# 15_BoardPowerSupply.net
KiCad netlist of a schematic drawn in Altium Designer
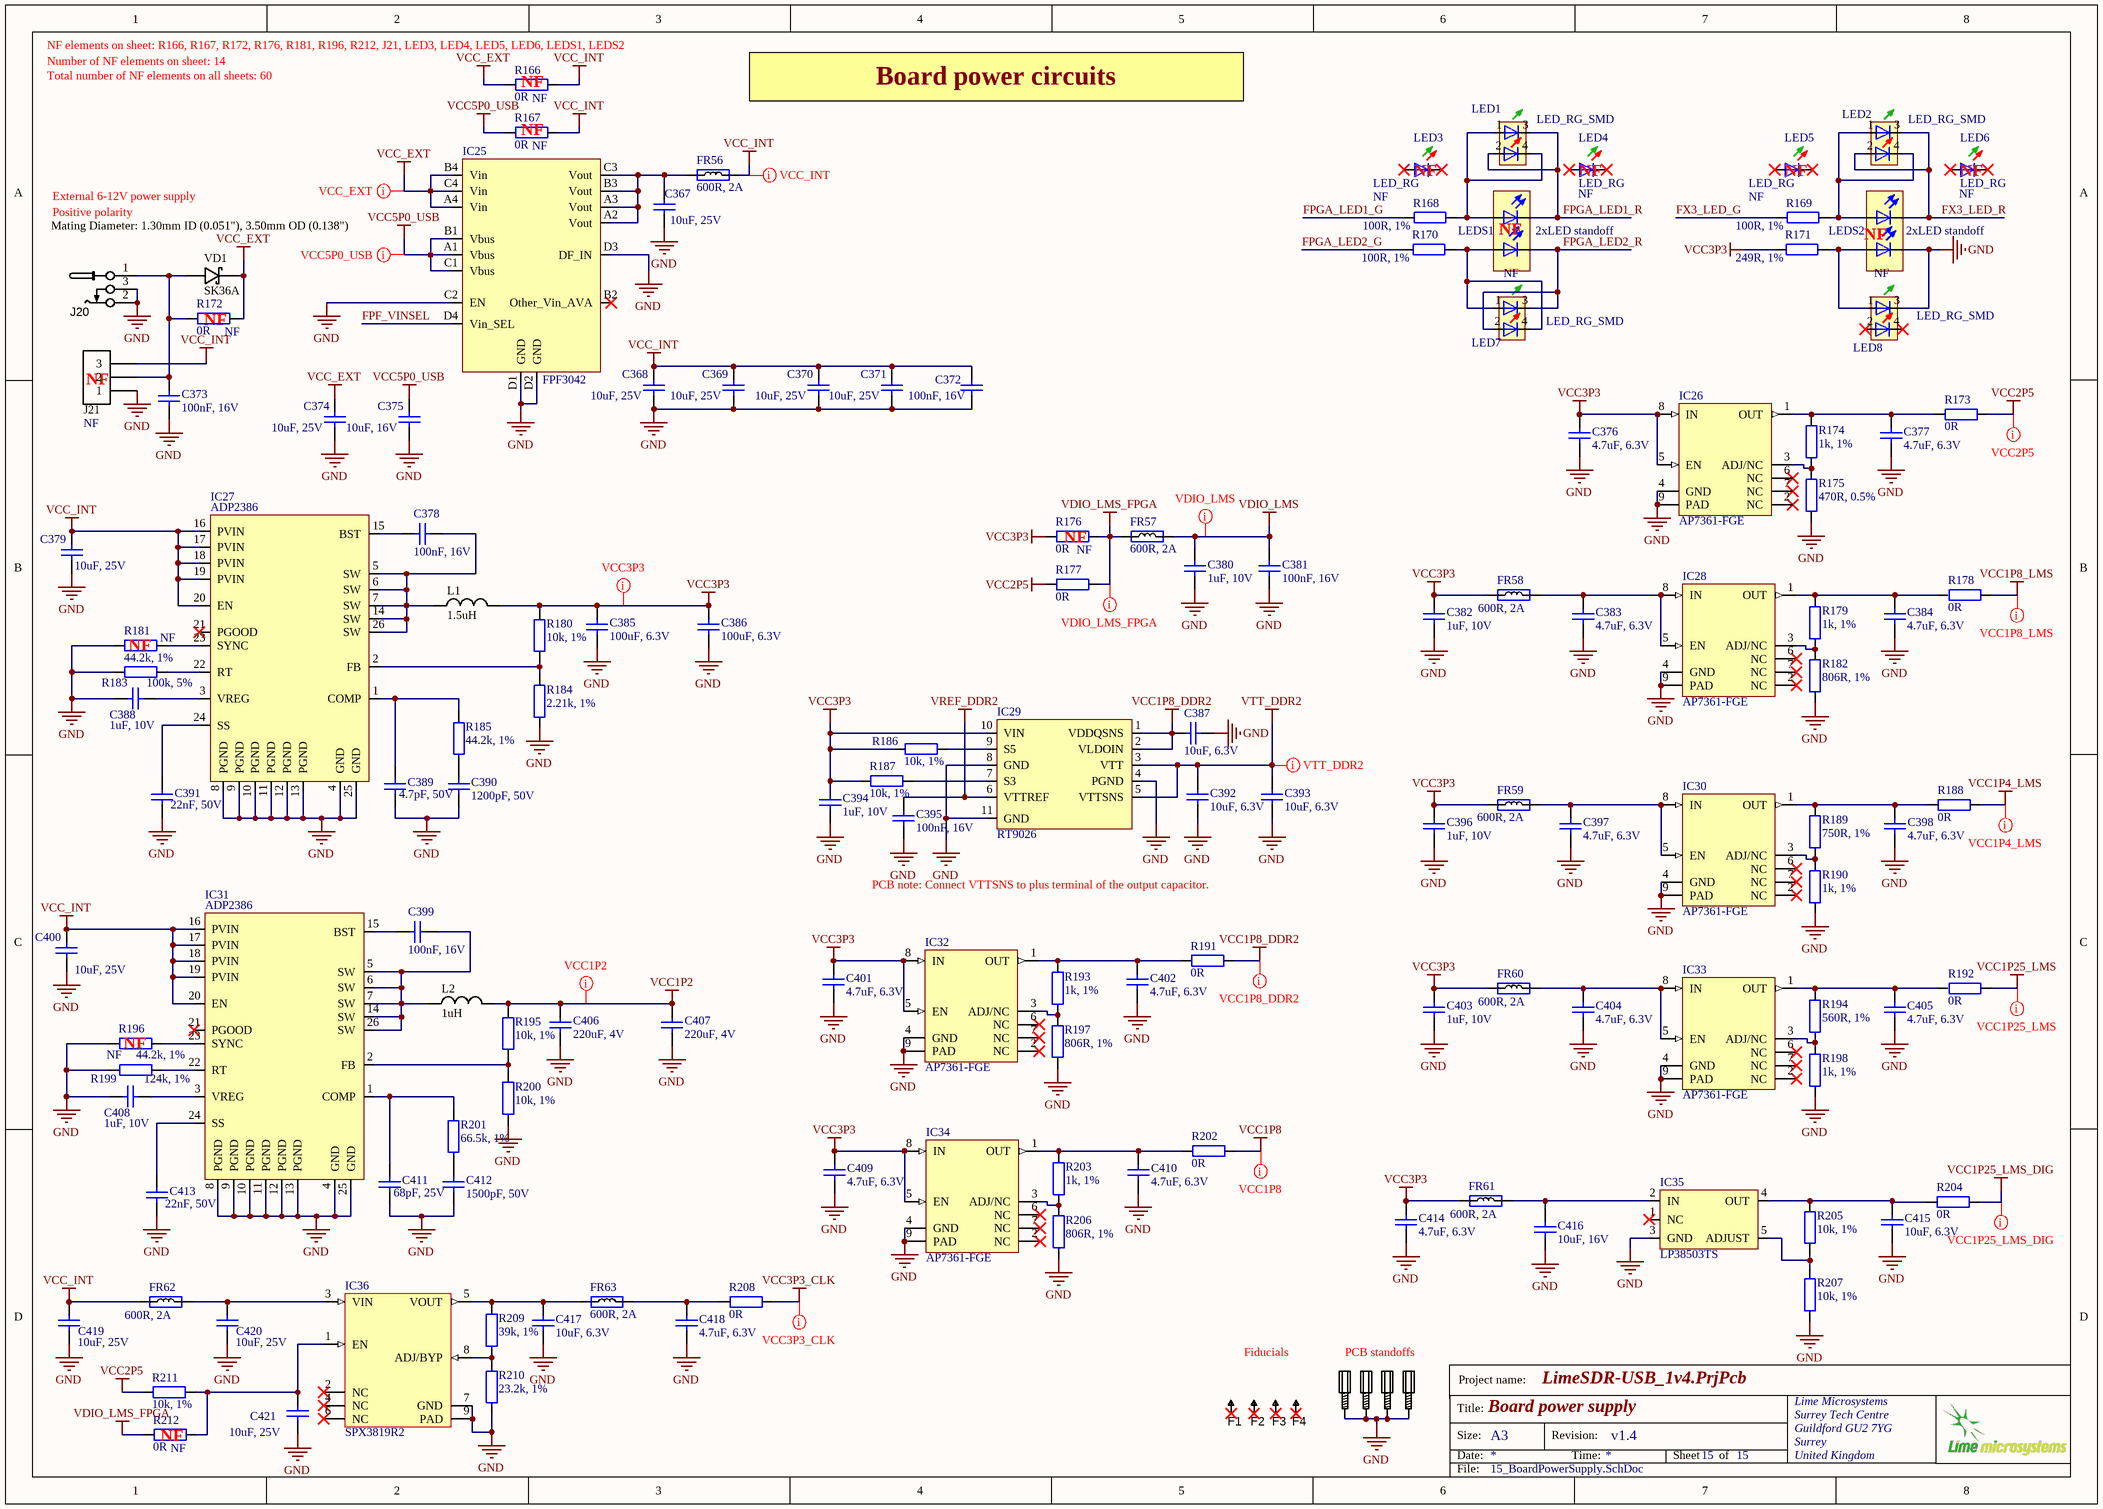
[diagram p0: 15_BoardPowerSupply.SchDoc]

(export (version "E")
  (design (tool "Eeschema 10.0.6"))
  (components
    (comp (ref "C367")
      (value "10uF, 25V")
      (footprint "CAP0603")
      (fields
        (field (name "MANUFACTURER") "Murata Electronics North America")
        (field (name "MANUFACTURER PART NUMBER") "GRM188R61E106MA73D")
        (field (name "TOLERANCE") "±20%")
      )
      (libsource (lib "LimeMicroAltiumLib_schLib") (part "Cap_0603"))
    )
    (comp (ref "C368")
      (value "10uF, 25V")
      (footprint "CAP0603")
      (fields
        (field (name "MANUFACTURER") "Murata Electronics North America")
        (field (name "MANUFACTURER PART NUMBER") "GRM188R61E106MA73D")
        (field (name "TOLERANCE") "±20%")
      )
      (libsource (lib "LimeMicroAltiumLib_schLib") (part "Cap_0603"))
    )
    (comp (ref "C369")
      (value "10uF, 25V")
      (footprint "CAP0603")
      (fields
        (field (name "MANUFACTURER") "Murata Electronics North America")
        (field (name "MANUFACTURER PART NUMBER") "GRM188R61E106MA73D")
        (field (name "TOLERANCE") "±20%")
      )
      (libsource (lib "LimeMicroAltiumLib_schLib") (part "Cap_0603"))
    )
    (comp (ref "C370")
      (value "10uF, 25V")
      (footprint "CAP0603")
      (fields
        (field (name "MANUFACTURER") "Murata Electronics North America")
        (field (name "MANUFACTURER PART NUMBER") "GRM188R61E106MA73D")
        (field (name "TOLERANCE") "±20%")
      )
      (libsource (lib "LimeMicroAltiumLib_schLib") (part "Cap_0603"))
    )
    (comp (ref "C371")
      (value "10uF, 25V")
      (footprint "CAP0603")
      (fields
        (field (name "MANUFACTURER") "Murata Electronics North America")
        (field (name "MANUFACTURER PART NUMBER") "GRM188R61E106MA73D")
        (field (name "TOLERANCE") "±20%")
      )
      (libsource (lib "LimeMicroAltiumLib_schLib") (part "Cap_0603"))
    )
    (comp (ref "C372")
      (value "100nF, 16V")
      (footprint "CAP0402")
      (fields
        (field (name "MANUFACTURER") "Murata Electronics")
        (field (name "TOLERANCE") "10 %")
        (field (name "MANUFACTURER PART NUMBER") "GRM155R71C104KA88D")
      )
      (libsource (lib "LimeMicroAltiumLib_schLib") (part "Cap_0402"))
    )
    (comp (ref "C373")
      (value "100nF, 16V")
      (footprint "CAP0402")
      (fields
        (field (name "MANUFACTURER") "Murata Electronics")
        (field (name "TOLERANCE") "10 %")
        (field (name "MANUFACTURER PART NUMBER") "GRM155R71C104KA88D")
      )
      (libsource (lib "LimeMicroAltiumLib_schLib") (part "Cap_0402"))
    )
    (comp (ref "C374")
      (value "10uF, 25V")
      (footprint "CAP0603")
      (fields
        (field (name "MANUFACTURER") "Murata Electronics North America")
        (field (name "MANUFACTURER PART NUMBER") "GRM188R61E106MA73D")
        (field (name "TOLERANCE") "±20%")
      )
      (libsource (lib "LimeMicroAltiumLib_schLib") (part "Cap_0603"))
    )
    (comp (ref "C375")
      (value "10uF, 16V")
      (footprint "CAP0603")
      (fields (field (name "MANUFACTURER") "Yageo") (field (name "TOLERANCE") "±20%"))
      (libsource (lib "LimeMicroAltiumLib_schLib") (part "Cap_0603"))
    )
    (comp (ref "C376")
      (value "4.7uF, 6.3V")
      (footprint "CAP0402")
      (fields
        (field (name "MANUFACTURER") "Murata Electronics North America")
        (field (name "TOLERANCE") "±20%")
        (field (name "MANUFACTURER PART NUMBER") "GRM155R60J475ME87D")
      )
      (libsource (lib "LimeMicroAltiumLib_schLib") (part "Cap_0402"))
    )
    (comp (ref "C377")
      (value "4.7uF, 6.3V")
      (footprint "CAP0402")
      (fields
        (field (name "MANUFACTURER") "Murata Electronics North America")
        (field (name "TOLERANCE") "±20%")
        (field (name "MANUFACTURER PART NUMBER") "GRM155R60J475ME87D")
      )
      (libsource (lib "LimeMicroAltiumLib_schLib") (part "Cap_0402"))
    )
    (comp (ref "C378")
      (value "100nF, 16V")
      (footprint "CAP0402")
      (fields
        (field (name "MANUFACTURER") "Murata Electronics")
        (field (name "TOLERANCE") "10 %")
        (field (name "MANUFACTURER PART NUMBER") "GRM155R71C104KA88D")
      )
      (libsource (lib "LimeMicroAltiumLib_schLib") (part "Cap_0402"))
    )
    (comp (ref "C379")
      (value "10uF, 25V")
      (footprint "CAP0603")
      (fields
        (field (name "MANUFACTURER") "Murata Electronics North America")
        (field (name "MANUFACTURER PART NUMBER") "GRM188R61E106MA73D")
        (field (name "TOLERANCE") "±20%")
      )
      (libsource (lib "LimeMicroAltiumLib_schLib") (part "Cap_0603"))
    )
    (comp (ref "C380")
      (value "1uF, 10V")
      (footprint "CAP0402")
      (fields (field (name "MANUFACTURER") "TDK"))
      (libsource (lib "LimeMicroAltiumLib_schLib") (part "Cap_0402"))
    )
    (comp (ref "C381")
      (value "100nF, 16V")
      (footprint "CAP0402")
      (fields
        (field (name "MANUFACTURER") "Murata Electronics")
        (field (name "TOLERANCE") "10 %")
        (field (name "MANUFACTURER PART NUMBER") "GRM155R71C104KA88D")
      )
      (libsource (lib "LimeMicroAltiumLib_schLib") (part "Cap_0402"))
    )
    (comp (ref "C382")
      (value "1uF, 10V")
      (footprint "CAP0402")
      (fields (field (name "MANUFACTURER") "TDK"))
      (libsource (lib "LimeMicroAltiumLib_schLib") (part "Cap_0402"))
    )
    (comp (ref "C383")
      (value "4.7uF, 6.3V")
      (footprint "CAP0402")
      (fields
        (field (name "MANUFACTURER") "Murata Electronics North America")
        (field (name "TOLERANCE") "±20%")
        (field (name "MANUFACTURER PART NUMBER") "GRM155R60J475ME87D")
      )
      (libsource (lib "LimeMicroAltiumLib_schLib") (part "Cap_0402"))
    )
    (comp (ref "C384")
      (value "4.7uF, 6.3V")
      (footprint "CAP0402")
      (fields
        (field (name "MANUFACTURER") "Murata Electronics North America")
        (field (name "TOLERANCE") "±20%")
        (field (name "MANUFACTURER PART NUMBER") "GRM155R60J475ME87D")
      )
      (libsource (lib "LimeMicroAltiumLib_schLib") (part "Cap_0402"))
    )
    (comp (ref "C385")
      (value "100uF, 6.3V")
      (footprint "CAP1206")
      (fields (field (name "MANUFACTURER") "Murata Electronics North America"))
      (libsource (lib "LimeFPGAboard_schLib") (part "Cap_1206"))
    )
    (comp (ref "C386")
      (value "100uF, 6.3V")
      (footprint "CAP1206")
      (fields (field (name "MANUFACTURER") "Murata Electronics North America"))
      (libsource (lib "LimeFPGAboard_schLib") (part "Cap_1206"))
    )
    (comp (ref "C387")
      (value "10uF, 6.3V")
      (footprint "CAP0603")
      (fields (field (name "TOLERANCE") "±20%") (field (name "MANUFACTURER") "Yageo"))
      (libsource (lib "LimeFPGAboard_schLib") (part "Cap_0603"))
    )
    (comp (ref "C388")
      (value "1uF, 10V")
      (footprint "CAP0402")
      (fields (field (name "MANUFACTURER") "TDK"))
      (libsource (lib "LimeMicroAltiumLib_schLib") (part "Cap_0402"))
    )
    (comp (ref "C389")
      (value "4.7pF, 50V")
      (footprint "CAP0402")
      (fields (field (name "MANUFACTURER") "Murata Electronics North America"))
      (libsource (lib "LimeMicroAltiumLib_schLib") (part "Cap_0402"))
    )
    (comp (ref "C390")
      (value "1200pF, 50V")
      (footprint "CAP0402")
      (fields (field (name "MANUFACTURER") "Kemet") (field (name "TOLERANCE") "±5%"))
      (libsource (lib "LimeMicroAltiumLib_schLib") (part "Cap_0402"))
    )
    (comp (ref "C391")
      (value "22nF, 50V")
      (footprint "CAP0402")
      (fields (field (name "TOLERANCE") "±10%") (field (name "MANUFACTURER") "Kemet"))
      (libsource (lib "LimeMicroAltiumLib_schLib") (part "Cap_0402"))
    )
    (comp (ref "C392")
      (value "10uF, 6.3V")
      (footprint "CAP0603")
      (fields (field (name "TOLERANCE") "±20%") (field (name "MANUFACTURER") "Yageo"))
      (libsource (lib "LimeFPGAboard_schLib") (part "Cap_0603"))
    )
    (comp (ref "C393")
      (value "10uF, 6.3V")
      (footprint "CAP0603")
      (fields (field (name "TOLERANCE") "±20%") (field (name "MANUFACTURER") "Yageo"))
      (libsource (lib "LimeFPGAboard_schLib") (part "Cap_0603"))
    )
    (comp (ref "C394")
      (value "1uF, 10V")
      (footprint "CAP0402")
      (fields (field (name "MANUFACTURER") "TDK"))
      (libsource (lib "LimeMicroAltiumLib_schLib") (part "Cap_0402"))
    )
    (comp (ref "C395")
      (value "100nF, 16V")
      (footprint "CAP0402")
      (fields
        (field (name "MANUFACTURER") "Murata Electronics")
        (field (name "TOLERANCE") "10 %")
        (field (name "MANUFACTURER PART NUMBER") "GRM155R71C104KA88D")
      )
      (libsource (lib "LimeMicroAltiumLib_schLib") (part "Cap_0402"))
    )
    (comp (ref "C396")
      (value "1uF, 10V")
      (footprint "CAP0402")
      (fields (field (name "MANUFACTURER") "TDK"))
      (libsource (lib "LimeMicroAltiumLib_schLib") (part "Cap_0402"))
    )
    (comp (ref "C397")
      (value "4.7uF, 6.3V")
      (footprint "CAP0402")
      (fields
        (field (name "MANUFACTURER") "Murata Electronics North America")
        (field (name "TOLERANCE") "±20%")
        (field (name "MANUFACTURER PART NUMBER") "GRM155R60J475ME87D")
      )
      (libsource (lib "LimeMicroAltiumLib_schLib") (part "Cap_0402"))
    )
    (comp (ref "C398")
      (value "4.7uF, 6.3V")
      (footprint "CAP0402")
      (fields
        (field (name "MANUFACTURER") "Murata Electronics North America")
        (field (name "TOLERANCE") "±20%")
        (field (name "MANUFACTURER PART NUMBER") "GRM155R60J475ME87D")
      )
      (libsource (lib "LimeMicroAltiumLib_schLib") (part "Cap_0402"))
    )
    (comp (ref "C399")
      (value "100nF, 16V")
      (footprint "CAP0402")
      (fields
        (field (name "MANUFACTURER") "Murata Electronics")
        (field (name "TOLERANCE") "10 %")
        (field (name "MANUFACTURER PART NUMBER") "GRM155R71C104KA88D")
      )
      (libsource (lib "LimeMicroAltiumLib_schLib") (part "Cap_0402"))
    )
    (comp (ref "C400")
      (value "10uF, 25V")
      (footprint "CAP0603")
      (fields
        (field (name "MANUFACTURER") "Murata Electronics North America")
        (field (name "MANUFACTURER PART NUMBER") "GRM188R61E106MA73D")
        (field (name "TOLERANCE") "±20%")
      )
      (libsource (lib "LimeMicroAltiumLib_schLib") (part "Cap_0603"))
    )
    (comp (ref "C401")
      (value "4.7uF, 6.3V")
      (footprint "CAP0402")
      (fields
        (field (name "MANUFACTURER") "Murata Electronics North America")
        (field (name "TOLERANCE") "±20%")
        (field (name "MANUFACTURER PART NUMBER") "GRM155R60J475ME87D")
      )
      (libsource (lib "LimeMicroAltiumLib_schLib") (part "Cap_0402"))
    )
    (comp (ref "C402")
      (value "4.7uF, 6.3V")
      (footprint "CAP0402")
      (fields
        (field (name "MANUFACTURER") "Murata Electronics North America")
        (field (name "TOLERANCE") "±20%")
        (field (name "MANUFACTURER PART NUMBER") "GRM155R60J475ME87D")
      )
      (libsource (lib "LimeMicroAltiumLib_schLib") (part "Cap_0402"))
    )
    (comp (ref "C403")
      (value "1uF, 10V")
      (footprint "CAP0402")
      (fields (field (name "MANUFACTURER") "TDK"))
      (libsource (lib "LimeMicroAltiumLib_schLib") (part "Cap_0402"))
    )
    (comp (ref "C404")
      (value "4.7uF, 6.3V")
      (footprint "CAP0402")
      (fields
        (field (name "MANUFACTURER") "Murata Electronics North America")
        (field (name "TOLERANCE") "±20%")
        (field (name "MANUFACTURER PART NUMBER") "GRM155R60J475ME87D")
      )
      (libsource (lib "LimeMicroAltiumLib_schLib") (part "Cap_0402"))
    )
    (comp (ref "C405")
      (value "4.7uF, 6.3V")
      (footprint "CAP0402")
      (fields
        (field (name "MANUFACTURER") "Murata Electronics North America")
        (field (name "TOLERANCE") "±20%")
        (field (name "MANUFACTURER PART NUMBER") "GRM155R60J475ME87D")
      )
      (libsource (lib "LimeMicroAltiumLib_schLib") (part "Cap_0402"))
    )
    (comp (ref "C406")
      (value "220uF, 4V")
      (footprint "CAP1206")
      (fields
        (field (name "MANUFACTURER") "Murata Electronics North America")
        (field (name "TOLERANCE") "±20%")
        (field (name "MANUFACTURER PART NUMBER") "GRM31CR60G227ME11L")
      )
      (libsource (lib "LimeFPGAboard_schLib") (part "Cap_1206"))
    )
    (comp (ref "C407")
      (value "220uF, 4V")
      (footprint "CAP1206")
      (fields
        (field (name "MANUFACTURER") "Murata Electronics North America")
        (field (name "TOLERANCE") "±20%")
        (field (name "MANUFACTURER PART NUMBER") "GRM31CR60G227ME11L")
      )
      (libsource (lib "LimeFPGAboard_schLib") (part "Cap_1206"))
    )
    (comp (ref "C408")
      (value "1uF, 10V")
      (footprint "CAP0402")
      (fields (field (name "MANUFACTURER") "TDK"))
      (libsource (lib "LimeMicroAltiumLib_schLib") (part "Cap_0402"))
    )
    (comp (ref "C409")
      (value "4.7uF, 6.3V")
      (footprint "CAP0402")
      (fields
        (field (name "MANUFACTURER") "Murata Electronics North America")
        (field (name "TOLERANCE") "±20%")
        (field (name "MANUFACTURER PART NUMBER") "GRM155R60J475ME87D")
      )
      (libsource (lib "LimeMicroAltiumLib_schLib") (part "Cap_0402"))
    )
    (comp (ref "C410")
      (value "4.7uF, 6.3V")
      (footprint "CAP0402")
      (fields
        (field (name "MANUFACTURER") "Murata Electronics North America")
        (field (name "TOLERANCE") "±20%")
        (field (name "MANUFACTURER PART NUMBER") "GRM155R60J475ME87D")
      )
      (libsource (lib "LimeMicroAltiumLib_schLib") (part "Cap_0402"))
    )
    (comp (ref "C411")
      (value "68pF, 25V")
      (footprint "CAP0402")
      (fields (field (name "TOLERANCE") "±1%") (field (name "MANUFACTURER") "Kemet"))
      (libsource (lib "LimeMicroAltiumLib_schLib") (part "Cap_0402"))
    )
    (comp (ref "C412")
      (value "1500pF, 50V")
      (footprint "CAP0402")
      (fields
        (field (name "MANUFACTURER") "Samsung Electro-Mechanics America, Inc.")
        (field (name "TOLERANCE") "±10%")
      )
      (libsource (lib "LimeMicroAltiumLib_schLib") (part "Cap_0402"))
    )
    (comp (ref "C413")
      (value "22nF, 50V")
      (footprint "CAP0402")
      (fields (field (name "TOLERANCE") "±10%") (field (name "MANUFACTURER") "Kemet"))
      (libsource (lib "LimeMicroAltiumLib_schLib") (part "Cap_0402"))
    )
    (comp (ref "C414")
      (value "4.7uF, 6.3V")
      (footprint "CAP0402")
      (fields
        (field (name "MANUFACTURER") "Murata Electronics North America")
        (field (name "TOLERANCE") "±20%")
        (field (name "MANUFACTURER PART NUMBER") "GRM155R60J475ME87D")
      )
      (libsource (lib "LimeMicroAltiumLib_schLib") (part "Cap_0402"))
    )
    (comp (ref "C415")
      (value "10uF, 6.3V")
      (footprint "CAP0603")
      (fields (field (name "TOLERANCE") "±20%") (field (name "MANUFACTURER") "Yageo"))
      (libsource (lib "LimeFPGAboard_schLib") (part "Cap_0603"))
    )
    (comp (ref "C416")
      (value "10uF, 16V")
      (footprint "CAP0603")
      (fields (field (name "MANUFACTURER") "Yageo") (field (name "TOLERANCE") "±20%"))
      (libsource (lib "LimeMicroAltiumLib_schLib") (part "Cap_0603"))
    )
    (comp (ref "C417")
      (value "10uF, 6.3V")
      (footprint "CAP0603")
      (fields (field (name "TOLERANCE") "±20%") (field (name "MANUFACTURER") "Yageo"))
      (libsource (lib "LimeFPGAboard_schLib") (part "Cap_0603"))
    )
    (comp (ref "C418")
      (value "4.7uF, 6.3V")
      (footprint "CAP0402")
      (fields
        (field (name "MANUFACTURER") "Murata Electronics North America")
        (field (name "TOLERANCE") "±20%")
        (field (name "MANUFACTURER PART NUMBER") "GRM155R60J475ME87D")
      )
      (libsource (lib "LimeMicroAltiumLib_schLib") (part "Cap_0402"))
    )
    (comp (ref "C419")
      (value "10uF, 25V")
      (footprint "CAP0603")
      (fields
        (field (name "MANUFACTURER") "Murata Electronics North America")
        (field (name "MANUFACTURER PART NUMBER") "GRM188R61E106MA73D")
        (field (name "TOLERANCE") "±20%")
      )
      (libsource (lib "LimeMicroAltiumLib_schLib") (part "Cap_0603"))
    )
    (comp (ref "C420")
      (value "10uF, 25V")
      (footprint "CAP0603")
      (fields
        (field (name "MANUFACTURER") "Murata Electronics North America")
        (field (name "MANUFACTURER PART NUMBER") "GRM188R61E106MA73D")
        (field (name "TOLERANCE") "±20%")
      )
      (libsource (lib "LimeMicroAltiumLib_schLib") (part "Cap_0603"))
    )
    (comp (ref "C421")
      (value "10uF, 25V")
      (footprint "CAP0603")
      (fields
        (field (name "MANUFACTURER") "Murata Electronics North America")
        (field (name "MANUFACTURER PART NUMBER") "GRM188R61E106MA73D")
        (field (name "TOLERANCE") "±20%")
      )
      (libsource (lib "LimeMicroAltiumLib_schLib") (part "Cap_0603"))
    )
    (comp (ref "F1")
      (value "Fiducial")
      (footprint "Fiducial")
      (libsource (lib "VGTU_Altium_lib") (part "Fiducial"))
    )
    (comp (ref "F2")
      (value "Fiducial")
      (footprint "Fiducial")
      (libsource (lib "VGTU_Altium_lib") (part "Fiducial"))
    )
    (comp (ref "F3")
      (value "Fiducial")
      (footprint "Fiducial")
      (libsource (lib "VGTU_Altium_lib") (part "Fiducial"))
    )
    (comp (ref "F4")
      (value "Fiducial")
      (footprint "Fiducial")
      (libsource (lib "VGTU_Altium_lib") (part "Fiducial"))
    )
    (comp (ref "FR56")
      (value "600R, 2A")
      (footprint "RES0805")
      (fields (field (name "MANUFACTURER") "TDK Corporation"))
      (libsource (lib "LimeFPGAboard_schLib") (part "Ferrite"))
    )
    (comp (ref "FR57")
      (value "600R, 2A")
      (footprint "RES0805")
      (fields (field (name "MANUFACTURER") "TDK Corporation"))
      (libsource (lib "LimeMicroAltiumLib_schLib") (part "Ferrite"))
    )
    (comp (ref "FR58")
      (value "600R, 2A")
      (footprint "RES0805")
      (fields (field (name "MANUFACTURER") "TDK Corporation"))
      (libsource (lib "LimeMicroAltiumLib_schLib") (part "Ferrite"))
    )
    (comp (ref "FR59")
      (value "600R, 2A")
      (footprint "RES0805")
      (fields (field (name "MANUFACTURER") "TDK Corporation"))
      (libsource (lib "LimeMicroAltiumLib_schLib") (part "Ferrite"))
    )
    (comp (ref "FR60")
      (value "600R, 2A")
      (footprint "RES0805")
      (fields (field (name "MANUFACTURER") "TDK Corporation"))
      (libsource (lib "LimeMicroAltiumLib_schLib") (part "Ferrite"))
    )
    (comp (ref "FR61")
      (value "600R, 2A")
      (footprint "RES0805")
      (fields (field (name "MANUFACTURER") "TDK Corporation"))
      (libsource (lib "LimeMicroAltiumLib_schLib") (part "Ferrite"))
    )
    (comp (ref "FR62")
      (value "600R, 2A")
      (footprint "RES0805")
      (fields (field (name "MANUFACTURER") "TDK Corporation"))
      (libsource (lib "LimeMicroAltiumLib_schLib") (part "Ferrite"))
    )
    (comp (ref "FR63")
      (value "600R, 2A")
      (footprint "RES0805")
      (fields (field (name "MANUFACTURER") "TDK Corporation"))
      (libsource (lib "LimeMicroAltiumLib_schLib") (part "Ferrite"))
    )
    (comp (ref "IC25")
      (value "FPF3042")
      (footprint "FPF3042")
      (fields (field (name "MANUFACTURER") "Fairchild Semiconductor"))
      (libsource (lib "LimeMicroAltiumLib_schLib") (part "FPF3042"))
    )
    (comp (ref "IC26")
      (value "AP7361-FGE")
      (footprint "AP7361")
      (fields
        (field (name "MANUFACTURER PART NUMBER") "AP7361-FGE-7")
        (field (name "MANUFACTURER") "Diodes Incorporated")
      )
      (libsource (lib "LimeMicroAltiumLib_schLib") (part "AP7361"))
    )
    (comp (ref "IC27")
      (value "ADP2386")
      (footprint "ADP2386")
      (fields
        (field (name "MANUFACTURER PART NUMBER") "ADP2386ACPZN-R7")
        (field (name "MANUFACTURER") "Analog Devices Inc.")
      )
      (libsource (lib "LimeMicroAltiumLib_schLib") (part "ADP2386"))
    )
    (comp (ref "IC28")
      (value "AP7361-FGE")
      (footprint "AP7361")
      (fields
        (field (name "MANUFACTURER PART NUMBER") "AP7361-FGE-7")
        (field (name "MANUFACTURER") "Diodes Incorporated")
      )
      (libsource (lib "LimeMicroAltiumLib_schLib") (part "AP7361"))
    )
    (comp (ref "IC29")
      (value "RT9026")
      (footprint "MSOP10")
      (fields (field (name "MANUFACTURER") "Richtek USA Inc."))
      (libsource (lib "LimeMicroAltiumLib_schLib") (part "RT9026"))
    )
    (comp (ref "IC30")
      (value "AP7361-FGE")
      (footprint "AP7361")
      (fields
        (field (name "MANUFACTURER PART NUMBER") "AP7361-FGE-7")
        (field (name "MANUFACTURER") "Diodes Incorporated")
      )
      (libsource (lib "LimeMicroAltiumLib_schLib") (part "AP7361"))
    )
    (comp (ref "IC31")
      (value "ADP2386")
      (footprint "ADP2386")
      (fields (field (name "MANUFACTURER") "Analog Devices Inc."))
      (libsource (lib "LimeMicroAltiumLib_schLib") (part "ADP2386"))
    )
    (comp (ref "IC32")
      (value "AP7361-FGE")
      (footprint "AP7361")
      (fields
        (field (name "MANUFACTURER PART NUMBER") "AP7361-FGE-7")
        (field (name "MANUFACTURER") "Diodes Incorporated")
      )
      (libsource (lib "LimeMicroAltiumLib_schLib") (part "AP7361"))
    )
    (comp (ref "IC33")
      (value "AP7361-FGE")
      (footprint "AP7361")
      (fields
        (field (name "MANUFACTURER PART NUMBER") "AP7361-FGE-7")
        (field (name "MANUFACTURER") "Diodes Incorporated")
      )
      (libsource (lib "LimeMicroAltiumLib_schLib") (part "AP7361"))
    )
    (comp (ref "IC34")
      (value "AP7361-FGE")
      (footprint "AP7361")
      (fields
        (field (name "MANUFACTURER PART NUMBER") "AP7361-FGE-7")
        (field (name "MANUFACTURER") "Diodes Incorporated")
      )
      (libsource (lib "LimeMicroAltiumLib_schLib") (part "AP7361"))
    )
    (comp (ref "IC35")
      (value "LP38503TS")
      (footprint "TO-263-5_v2")
      (fields
        (field (name "MANUFACTURER PART NUMBER") "LP38503TS-ADJ/NOPB")
        (field (name "MANUFACTURER") "Texas Instruments")
      )
      (libsource (lib "LimeMicroAltiumLib_schLib") (part "LP38503TS"))
    )
    (comp (ref "IC36")
      (value "SPX3819R2")
      (footprint "SPX3819R2-L/TR")
      (fields (field (name "MANUFACTURER") "Exar Corporation"))
      (libsource (lib "LimeMicroAltiumLib_schLib") (part "SPX3819R2-L/TR"))
    )
    (comp (ref "J20")
      (value "Mating Diameter: 1.30mm ID (0.051\"), 3.50mm OD (0.138\")")
      (footprint "CONN_PWR_JACK_v4")
      (fields (field (name "MANUFACTURER") "CUI Inc."))
      (libsource (lib "LimeFPGAboard_schLib") (part "CONN_PWR_JACK_2.1x5.5mm"))
    )
    (comp (ref "J21")
      (value "Header 3x1 pin")
      (footprint "HDR_1x3")
      (description "Header, 3-pin")
      (fields (field (name "ASSEMBLY INFO") "NF") (field (name "MANUFACTURER") "Amphenol FCI"))
      (libsource (lib "LimeMicroAltiumLib_schLib") (part "Header3P"))
    )
    (comp (ref "L1")
      (value "1.5uH")
      (footprint "FDVE1040_TOKO_INDUCTOR")
      (fields (field (name "MANUFACTURER") "Vishay Dale") (field (name "TOLERANCE") "±20%"))
      (libsource (lib "LimeMicroAltiumLib_schLib") (part "Inductor_0603"))
    )
    (comp (ref "L2")
      (value "1uH")
      (footprint "FDVE1040_TOKO_INDUCTOR")
      (fields (field (name "TOLERANCE") "±20%") (field (name "MANUFACTURER") "Vishay Dale"))
      (libsource (lib "LimeMicroAltiumLib_schLib") (part "Inductor_0603"))
    )
    (comp (ref "LED1")
      (value "LED_RG_SMD")
      (footprint "LED-2x0603")
      (fields (field (name "MANUFACTURER") "Avago Technologies US Inc."))
      (libsource (lib "LimeMicroAltiumLib_schLib") (part "LED_green_red_SMD"))
    )
    (comp (ref "LED2")
      (value "LED_RG_SMD")
      (footprint "LED-2x0603")
      (fields (field (name "MANUFACTURER") "Avago Technologies US Inc."))
      (libsource (lib "LimeMicroAltiumLib_schLib") (part "LED_green_red_SMD"))
    )
    (comp (ref "LED3")
      (value "LED_RG")
      (fields
        (field (name "MANUFACTURER") "Visual Communications Company - VCC")
        (field (name "ASSEMBLY INFO") "NF")
      )
      (libsource (lib "LimeMicroAltiumLib_schLib") (part "LED_green_red"))
    )
    (comp (ref "LED4")
      (value "LED_RG")
      (fields
        (field (name "MANUFACTURER") "Visual Communications Company - VCC")
        (field (name "ASSEMBLY INFO") "NF")
      )
      (libsource (lib "LimeMicroAltiumLib_schLib") (part "LED_green_red"))
    )
    (comp (ref "LED5")
      (value "LED_RG")
      (fields
        (field (name "MANUFACTURER") "Visual Communications Company - VCC")
        (field (name "ASSEMBLY INFO") "NF")
      )
      (libsource (lib "LimeMicroAltiumLib_schLib") (part "LED_green_red"))
    )
    (comp (ref "LED6")
      (value "LED_RG")
      (fields
        (field (name "MANUFACTURER") "Visual Communications Company - VCC")
        (field (name "ASSEMBLY INFO") "NF")
      )
      (libsource (lib "LimeMicroAltiumLib_schLib") (part "LED_green_red"))
    )
    (comp (ref "LED7")
      (value "LED_RG_SMD")
      (footprint "LED-2x0603")
      (fields (field (name "MANUFACTURER") "Avago Technologies US Inc."))
      (libsource (lib "LimeMicroAltiumLib_schLib") (part "LED_green_red_SMD"))
    )
    (comp (ref "LED8")
      (value "LED_RG_SMD")
      (footprint "LED-2x0603")
      (fields (field (name "MANUFACTURER") "Avago Technologies US Inc."))
      (libsource (lib "LimeMicroAltiumLib_schLib") (part "LED_green_red_SMD"))
    )
    (comp (ref "LEDS1")
      (value "2xLED standoff")
      (footprint "LED_STANDOFF_H-201C")
      (fields (field (name "MANUFACTURER") "Bivar Inc.") (field (name "ASSEMBLY INFO") "NF"))
      (libsource (lib "LimeMicroAltiumLib_schLib") (part "LEDx2_STANDOFF"))
    )
    (comp (ref "LEDS2")
      (value "2xLED standoff")
      (footprint "LED_STANDOFF_H-201C")
      (fields (field (name "MANUFACTURER") "Bivar Inc.") (field (name "ASSEMBLY INFO") "NF"))
      (libsource (lib "LimeMicroAltiumLib_schLib") (part "LEDx2_STANDOFF"))
    )
    (comp (ref "MECH1")
      (value "# pcs.")
      (footprint "PCB_standoff")
      (description "STANDOFF M/F MET 5MM HEX 10MM L")
      (fields (field (name "MANUFACTURER") "FIX&FASTEN"))
      (libsource (lib "LimeMicroAltiumLib_schLib") (part "STANDOFF_M-F_THREADED_M3x8x10mm_HEX_5mm dia"))
    )
    (comp (ref "MECH2")
      (value "# pcs.")
      (footprint "PCB_standoff")
      (description "STANDOFF M/F MET 5MM HEX 10MM L")
      (fields (field (name "MANUFACTURER") "FIX&FASTEN"))
      (libsource (lib "LimeMicroAltiumLib_schLib") (part "STANDOFF_M-F_THREADED_M3x8x10mm_HEX_5mm dia"))
    )
    (comp (ref "MECH3")
      (value "# pcs.")
      (footprint "PCB_standoff")
      (description "STANDOFF M/F MET 5MM HEX 10MM L")
      (fields (field (name "MANUFACTURER") "FIX&FASTEN"))
      (libsource (lib "LimeMicroAltiumLib_schLib") (part "STANDOFF_M-F_THREADED_M3x8x10mm_HEX_5mm dia"))
    )
    (comp (ref "MECH4")
      (value "# pcs.")
      (footprint "PCB_standoff")
      (description "STANDOFF M/F MET 5MM HEX 10MM L")
      (fields (field (name "MANUFACTURER") "FIX&FASTEN"))
      (libsource (lib "LimeMicroAltiumLib_schLib") (part "STANDOFF_M-F_THREADED_M3x8x10mm_HEX_5mm dia"))
    )
    (comp (ref "R166")
      (value "0R")
      (footprint "RES0402")
      (fields
        (field (name "ASSEMBLY INFO") "NF")
        (field (name "MANUFACTURER") "Yageo")
        (field (name "TOLERANCE") "Jumper")
      )
      (libsource (lib "LimeMicroAltiumLib_schLib") (part "Res_0402"))
    )
    (comp (ref "R167")
      (value "0R")
      (footprint "RES0402")
      (fields
        (field (name "ASSEMBLY INFO") "NF")
        (field (name "MANUFACTURER") "Yageo")
        (field (name "TOLERANCE") "Jumper")
      )
      (libsource (lib "LimeMicroAltiumLib_schLib") (part "Res_0402"))
    )
    (comp (ref "R168")
      (value "100R, 1%")
      (footprint "RES0402")
      (fields (field (name "TOLERANCE") "±1%") (field (name "MANUFACTURER") "Stackpole Electronics Inc."))
      (libsource (lib "LimeMicroAltiumLib_schLib") (part "Res_0402"))
    )
    (comp (ref "R169")
      (value "100R, 1%")
      (footprint "RES0402")
      (fields (field (name "TOLERANCE") "±1%") (field (name "MANUFACTURER") "Stackpole Electronics Inc."))
      (libsource (lib "LimeMicroAltiumLib_schLib") (part "Res_0402"))
    )
    (comp (ref "R170")
      (value "100R, 1%")
      (footprint "RES0402")
      (fields (field (name "TOLERANCE") "±1%") (field (name "MANUFACTURER") "Stackpole Electronics Inc."))
      (libsource (lib "LimeMicroAltiumLib_schLib") (part "Res_0402"))
    )
    (comp (ref "R171")
      (value "249R, 1%")
      (footprint "RES0402")
      (fields (field (name "MANUFACTURER") "Stackpole Electronics Inc") (field (name "TOLERANCE") "±1%"))
      (libsource (lib "LimeMicroAltiumLib_schLib") (part "Res_0402"))
    )
    (comp (ref "R172")
      (value "0R")
      (footprint "RES0805")
      (fields
        (field (name "ASSEMBLY INFO") "NF")
        (field (name "MANUFACTURER") "Vishay Dale")
        (field (name "TOLERANCE") "Jumper")
      )
      (libsource (lib "LimeMicroAltiumLib_schLib") (part "Res_0402"))
    )
    (comp (ref "R173")
      (value "0R")
      (footprint "RES0402")
      (fields (field (name "MANUFACTURER") "Yageo") (field (name "TOLERANCE") "Jumper"))
      (libsource (lib "LimeMicroAltiumLib_schLib") (part "Res_0402"))
    )
    (comp (ref "R174")
      (value "1k, 1%")
      (footprint "RES0402")
      (fields (field (name "MANUFACTURER") "Stackpole Electronics Inc") (field (name "TOLERANCE") "±1%"))
      (libsource (lib "LimeMicroAltiumLib_schLib") (part "Res_0402"))
    )
    (comp (ref "R175")
      (value "470R, 0.5%")
      (footprint "RES0402")
      (fields
        (field (name "TOLERANCE") "±0.5%")
        (field (name "MANUFACTURER") "Panasonic Electronic Components")
      )
      (libsource (lib "LimeMicroAltiumLib_schLib") (part "Res_0402"))
    )
    (comp (ref "R176")
      (value "0R")
      (footprint "RES0402")
      (fields
        (field (name "ASSEMBLY INFO") "NF")
        (field (name "MANUFACTURER") "Yageo")
        (field (name "TOLERANCE") "Jumper")
      )
      (libsource (lib "LimeMicroAltiumLib_schLib") (part "Res_0402"))
    )
    (comp (ref "R177")
      (value "0R")
      (footprint "RES0402")
      (fields (field (name "MANUFACTURER") "Yageo") (field (name "TOLERANCE") "Jumper"))
      (libsource (lib "LimeMicroAltiumLib_schLib") (part "Res_0402"))
    )
    (comp (ref "R178")
      (value "0R")
      (footprint "RES0402")
      (fields (field (name "MANUFACTURER") "Yageo") (field (name "TOLERANCE") "Jumper"))
      (libsource (lib "LimeMicroAltiumLib_schLib") (part "Res_0402"))
    )
    (comp (ref "R179")
      (value "1k, 1%")
      (footprint "RES0402")
      (fields (field (name "MANUFACTURER") "Stackpole Electronics Inc") (field (name "TOLERANCE") "±1%"))
      (libsource (lib "LimeMicroAltiumLib_schLib") (part "Res_0402"))
    )
    (comp (ref "R180")
      (value "10k, 1%")
      (footprint "RES0402")
      (fields (field (name "MANUFACTURER") "Yageo") (field (name "TOLERANCE") "±1%"))
      (libsource (lib "LimeMicroAltiumLib_schLib") (part "Res_0402"))
    )
    (comp (ref "R181")
      (value "44.2k, 1%")
      (footprint "RES0402")
      (fields
        (field (name "ASSEMBLY INFO") "NF")
        (field (name "TOLERANCE") "±1%")
        (field (name "MANUFACTURER") "Panasonic Electronic Components")
      )
      (libsource (lib "LimeMicroAltiumLib_schLib") (part "Res_0402"))
    )
    (comp (ref "R182")
      (value "806R, 1%")
      (footprint "RES0402")
      (fields (field (name "TOLERANCE") "±1%") (field (name "MANUFACTURER") "Stackpole Electronics Inc"))
      (libsource (lib "LimeMicroAltiumLib_schLib") (part "Res_0402"))
    )
    (comp (ref "R183")
      (value "100k, 5%")
      (footprint "RES0402")
      (fields
        (field (name "MANUFACTURER") "Panasonic Electronic Components")
        (field (name "MANUFACTURER PART NUMBER") "ERJ-2GEJ104X")
        (field (name "TOLERANCE") "±5%")
      )
      (libsource (lib "LimeMicroAltiumLib_schLib") (part "Res_0402"))
    )
    (comp (ref "R184")
      (value "2.21k, 1%")
      (footprint "RES0402")
      (fields (field (name "MANUFACTURER") "Stackpole Electronics Inc.") (field (name "TOLERANCE") "±1%"))
      (libsource (lib "LimeMicroAltiumLib_schLib") (part "Res_0402"))
    )
    (comp (ref "R185")
      (value "44.2k, 1%")
      (footprint "RES0402")
      (fields
        (field (name "TOLERANCE") "±1%")
        (field (name "MANUFACTURER") "Panasonic Electronic Components")
      )
      (libsource (lib "LimeMicroAltiumLib_schLib") (part "Res_0402"))
    )
    (comp (ref "R186")
      (value "10k, 1%")
      (footprint "RES0402")
      (fields (field (name "MANUFACTURER") "Yageo") (field (name "TOLERANCE") "±1%"))
      (libsource (lib "LimeMicroAltiumLib_schLib") (part "Res_0402"))
    )
    (comp (ref "R187")
      (value "10k, 1%")
      (footprint "RES0402")
      (fields (field (name "MANUFACTURER") "Yageo") (field (name "TOLERANCE") "±1%"))
      (libsource (lib "LimeMicroAltiumLib_schLib") (part "Res_0402"))
    )
    (comp (ref "R188")
      (value "0R")
      (footprint "RES0402")
      (fields (field (name "MANUFACTURER") "Yageo") (field (name "TOLERANCE") "Jumper"))
      (libsource (lib "LimeMicroAltiumLib_schLib") (part "Res_0402"))
    )
    (comp (ref "R189")
      (value "750R, 1%")
      (footprint "RES0402")
      (fields
        (field (name "TOLERANCE") "±1%")
        (field (name "MANUFACTURER PART NUMBER") "RC0402FR-07750RL")
        (field (name "MANUFACTURER") "Yageo")
      )
      (libsource (lib "LimeMicroAltiumLib_schLib") (part "Res_0402"))
    )
    (comp (ref "R190")
      (value "1k, 1%")
      (footprint "RES0402")
      (fields (field (name "MANUFACTURER") "Stackpole Electronics Inc") (field (name "TOLERANCE") "±1%"))
      (libsource (lib "LimeMicroAltiumLib_schLib") (part "Res_0402"))
    )
    (comp (ref "R191")
      (value "0R")
      (footprint "RES0402")
      (fields (field (name "MANUFACTURER") "Yageo") (field (name "TOLERANCE") "Jumper"))
      (libsource (lib "LimeMicroAltiumLib_schLib") (part "Res_0402"))
    )
    (comp (ref "R192")
      (value "0R")
      (footprint "RES0402")
      (fields (field (name "MANUFACTURER") "Yageo") (field (name "TOLERANCE") "Jumper"))
      (libsource (lib "LimeMicroAltiumLib_schLib") (part "Res_0402"))
    )
    (comp (ref "R193")
      (value "1k, 1%")
      (footprint "RES0402")
      (fields (field (name "MANUFACTURER") "Stackpole Electronics Inc") (field (name "TOLERANCE") "±1%"))
      (libsource (lib "LimeMicroAltiumLib_schLib") (part "Res_0402"))
    )
    (comp (ref "R194")
      (value "560R, 1%")
      (footprint "RES0402")
      (fields
        (field (name "MANUFACTURER PART NUMBER") "CRCW0402560RFKED")
        (field (name "TOLERANCE") "±1%")
        (field (name "MANUFACTURER") "Vishay Dale")
      )
      (libsource (lib "LimeMicroAltiumLib_schLib") (part "Res_0402"))
    )
    (comp (ref "R195")
      (value "10k, 1%")
      (footprint "RES0402")
      (fields (field (name "MANUFACTURER") "Yageo") (field (name "TOLERANCE") "±1%"))
      (libsource (lib "LimeMicroAltiumLib_schLib") (part "Res_0402"))
    )
    (comp (ref "R196")
      (value "44.2k, 1%")
      (footprint "RES0402")
      (fields
        (field (name "ASSEMBLY INFO") "NF")
        (field (name "TOLERANCE") "±1%")
        (field (name "MANUFACTURER") "Panasonic Electronic Components")
      )
      (libsource (lib "LimeMicroAltiumLib_schLib") (part "Res_0402"))
    )
    (comp (ref "R197")
      (value "806R, 1%")
      (footprint "RES0402")
      (fields (field (name "TOLERANCE") "±1%") (field (name "MANUFACTURER") "Stackpole Electronics Inc"))
      (libsource (lib "LimeMicroAltiumLib_schLib") (part "Res_0402"))
    )
    (comp (ref "R198")
      (value "1k, 1%")
      (footprint "RES0402")
      (fields (field (name "MANUFACTURER") "Stackpole Electronics Inc") (field (name "TOLERANCE") "±1%"))
      (libsource (lib "LimeMicroAltiumLib_schLib") (part "Res_0402"))
    )
    (comp (ref "R199")
      (value "124k, 1%")
      (footprint "RES0402")
      (fields
        (field (name "MANUFACTURER") "Panasonic Electronic Components")
        (field (name "TOLERANCE") "±1%")
      )
      (libsource (lib "LimeMicroAltiumLib_schLib") (part "Res_0402"))
    )
    (comp (ref "R200")
      (value "10k, 1%")
      (footprint "RES0402")
      (fields (field (name "MANUFACTURER") "Yageo") (field (name "TOLERANCE") "±1%"))
      (libsource (lib "LimeMicroAltiumLib_schLib") (part "Res_0402"))
    )
    (comp (ref "R201")
      (value "66.5k, 1%")
      (footprint "RES0402")
      (fields
        (field (name "MANUFACTURER") "Panasonic Electronic Components")
        (field (name "TOLERANCE") "±1%")
      )
      (libsource (lib "LimeMicroAltiumLib_schLib") (part "Res_0402"))
    )
    (comp (ref "R202")
      (value "0R")
      (footprint "RES0402")
      (fields (field (name "MANUFACTURER") "Yageo") (field (name "TOLERANCE") "Jumper"))
      (libsource (lib "LimeMicroAltiumLib_schLib") (part "Res_0402"))
    )
    (comp (ref "R203")
      (value "1k, 1%")
      (footprint "RES0402")
      (fields (field (name "MANUFACTURER") "Stackpole Electronics Inc") (field (name "TOLERANCE") "±1%"))
      (libsource (lib "LimeMicroAltiumLib_schLib") (part "Res_0402"))
    )
    (comp (ref "R204")
      (value "0R")
      (footprint "RES0402")
      (fields (field (name "MANUFACTURER") "Yageo") (field (name "TOLERANCE") "Jumper"))
      (libsource (lib "LimeMicroAltiumLib_schLib") (part "Res_0402"))
    )
    (comp (ref "R205")
      (value "10k, 1%")
      (footprint "RES0402")
      (fields (field (name "MANUFACTURER") "Yageo") (field (name "TOLERANCE") "±1%"))
      (libsource (lib "LimeMicroAltiumLib_schLib") (part "Res_0402"))
    )
    (comp (ref "R206")
      (value "806R, 1%")
      (footprint "RES0402")
      (fields (field (name "TOLERANCE") "±1%") (field (name "MANUFACTURER") "Stackpole Electronics Inc"))
      (libsource (lib "LimeMicroAltiumLib_schLib") (part "Res_0402"))
    )
    (comp (ref "R207")
      (value "10k, 1%")
      (footprint "RES0402")
      (fields (field (name "MANUFACTURER") "Yageo") (field (name "TOLERANCE") "±1%"))
      (libsource (lib "LimeMicroAltiumLib_schLib") (part "Res_0402"))
    )
    (comp (ref "R208")
      (value "0R")
      (footprint "RES0402")
      (fields (field (name "MANUFACTURER") "Yageo") (field (name "TOLERANCE") "Jumper"))
      (libsource (lib "LimeMicroAltiumLib_schLib") (part "Res_0402"))
    )
    (comp (ref "R209")
      (value "39k, 1%")
      (footprint "RES0402")
      (fields (field (name "MANUFACTURER") "Yageo") (field (name "TOLERANCE") "±1%"))
      (libsource (lib "LimeMicroAltiumLib_schLib") (part "Res_0402"))
    )
    (comp (ref "R210")
      (value "23.2k, 1%")
      (footprint "RES0402")
      (fields (field (name "TOLERANCE") "±1%") (field (name "MANUFACTURER") "Yageo"))
      (libsource (lib "LimeMicroAltiumLib_schLib") (part "Res_0402"))
    )
    (comp (ref "R211")
      (value "10k, 1%")
      (footprint "RES0402")
      (fields (field (name "MANUFACTURER") "Yageo") (field (name "TOLERANCE") "±1%"))
      (libsource (lib "LimeMicroAltiumLib_schLib") (part "Res_0402"))
    )
    (comp (ref "R212")
      (value "0R")
      (footprint "RES0402")
      (fields
        (field (name "ASSEMBLY INFO") "NF")
        (field (name "MANUFACTURER") "Yageo")
        (field (name "TOLERANCE") "Jumper")
      )
      (libsource (lib "LimeMicroAltiumLib_schLib") (part "Res_0402"))
    )
    (comp (ref "VD1")
      (value "SK36A")
      (footprint "DIODE_SMB")
      (description "Diode Schottky SMD SOD-523F")
      (fields (field (name "MANUFACTURER") "Micro Commercial Co"))
      (libsource (lib "LimeMicroAltiumLib_schLib") (part "DIODE_SCHOTTKY_SOD-523F"))
    )
  )
  (nets
    (net (code "1") (name "/FPF_VINSEL") (class "Default")
      (node (ref "IC25") (pin "D4") (pinfunction "Vin_SEL_D4") (pintype "passive"))
    )
    (net (code "2") (name "/FPGA_LED1_G") (class "Default")
      (node (ref "R168") (pin "1") (pinfunction "1_1") (pintype "passive"))
    )
    (net (code "3") (name "/FPGA_LED1_R") (class "Default")
      (node (ref "LED1") (pin "2") (pinfunction "2_2") (pintype "power_in"))
      (node (ref "LED1") (pin "3") (pinfunction "3_3") (pintype "power_in"))
      (node (ref "LEDS1") (pin "K1") (pinfunction "C_K1") (pintype "power_in"))
    )
    (net (code "4") (name "/FPGA_LED2_G") (class "Default")
      (node (ref "R170") (pin "1") (pinfunction "1_1") (pintype "passive"))
    )
    (net (code "5") (name "/FPGA_LED2_R") (class "Default")
      (node (ref "LED7") (pin "2") (pinfunction "2_2") (pintype "power_in"))
      (node (ref "LED7") (pin "3") (pinfunction "3_3") (pintype "power_in"))
      (node (ref "LEDS1") (pin "K2") (pinfunction "C_K2") (pintype "power_in"))
    )
    (net (code "6") (name "/FX3_LED_G") (class "Default")
      (node (ref "R169") (pin "1") (pinfunction "1_1") (pintype "passive"))
    )
    (net (code "7") (name "/FX3_LED_R") (class "Default")
      (node (ref "LED2") (pin "2") (pinfunction "2_2") (pintype "power_in"))
      (node (ref "LED2") (pin "3") (pinfunction "3_3") (pintype "power_in"))
      (node (ref "LEDS2") (pin "K1") (pinfunction "C_K1") (pintype "power_in"))
    )
    (net (code "8") (name "GND") (class "Default")
      (node (ref "C367") (pin "1") (pinfunction "1_1") (pintype "passive"))
      (node (ref "C368") (pin "1") (pinfunction "1_1") (pintype "passive"))
      (node (ref "C369") (pin "1") (pinfunction "1_1") (pintype "passive"))
      (node (ref "C370") (pin "1") (pinfunction "1_1") (pintype "passive"))
      (node (ref "C371") (pin "1") (pinfunction "1_1") (pintype "passive"))
      (node (ref "C372") (pin "2") (pinfunction "2_2") (pintype "passive"))
      (node (ref "C373") (pin "2") (pinfunction "2_2") (pintype "passive"))
      (node (ref "C374") (pin "1") (pinfunction "1_1") (pintype "passive"))
      (node (ref "C375") (pin "1") (pinfunction "1_1") (pintype "passive"))
      (node (ref "C376") (pin "1") (pinfunction "1_1") (pintype "passive"))
      (node (ref "C377") (pin "1") (pinfunction "1_1") (pintype "passive"))
      (node (ref "C379") (pin "1") (pinfunction "1_1") (pintype "passive"))
      (node (ref "C380") (pin "1") (pinfunction "1_1") (pintype "passive"))
      (node (ref "C381") (pin "2") (pinfunction "2_2") (pintype "passive"))
      (node (ref "C382") (pin "1") (pinfunction "1_1") (pintype "passive"))
      (node (ref "C383") (pin "1") (pinfunction "1_1") (pintype "passive"))
      (node (ref "C384") (pin "1") (pinfunction "1_1") (pintype "passive"))
      (node (ref "C385") (pin "1") (pinfunction "1_1") (pintype "passive"))
      (node (ref "C386") (pin "1") (pinfunction "1_1") (pintype "passive"))
      (node (ref "C387") (pin "1") (pinfunction "1_1") (pintype "passive"))
      (node (ref "C388") (pin "2") (pinfunction "2_2") (pintype "passive"))
      (node (ref "C389") (pin "2") (pinfunction "2_2") (pintype "passive"))
      (node (ref "C390") (pin "2") (pinfunction "2_2") (pintype "passive"))
      (node (ref "C391") (pin "2") (pinfunction "2_2") (pintype "passive"))
      (node (ref "C392") (pin "1") (pinfunction "1_1") (pintype "passive"))
      (node (ref "C393") (pin "1") (pinfunction "1_1") (pintype "passive"))
      (node (ref "C394") (pin "1") (pinfunction "1_1") (pintype "passive"))
      (node (ref "C395") (pin "2") (pinfunction "2_2") (pintype "passive"))
      (node (ref "C396") (pin "1") (pinfunction "1_1") (pintype "passive"))
      (node (ref "C397") (pin "1") (pinfunction "1_1") (pintype "passive"))
      (node (ref "C398") (pin "1") (pinfunction "1_1") (pintype "passive"))
      (node (ref "C400") (pin "1") (pinfunction "1_1") (pintype "passive"))
      (node (ref "C401") (pin "1") (pinfunction "1_1") (pintype "passive"))
      (node (ref "C402") (pin "1") (pinfunction "1_1") (pintype "passive"))
      (node (ref "C403") (pin "1") (pinfunction "1_1") (pintype "passive"))
      (node (ref "C404") (pin "1") (pinfunction "1_1") (pintype "passive"))
      (node (ref "C405") (pin "1") (pinfunction "1_1") (pintype "passive"))
      (node (ref "C406") (pin "1") (pinfunction "1_1") (pintype "passive"))
      (node (ref "C407") (pin "1") (pinfunction "1_1") (pintype "passive"))
      (node (ref "C408") (pin "2") (pinfunction "2_2") (pintype "passive"))
      (node (ref "C409") (pin "1") (pinfunction "1_1") (pintype "passive"))
      (node (ref "C410") (pin "1") (pinfunction "1_1") (pintype "passive"))
      (node (ref "C411") (pin "2") (pinfunction "2_2") (pintype "passive"))
      (node (ref "C412") (pin "2") (pinfunction "2_2") (pintype "passive"))
      (node (ref "C413") (pin "2") (pinfunction "2_2") (pintype "passive"))
      (node (ref "C414") (pin "1") (pinfunction "1_1") (pintype "passive"))
      (node (ref "C415") (pin "1") (pinfunction "1_1") (pintype "passive"))
      (node (ref "C416") (pin "1") (pinfunction "1_1") (pintype "passive"))
      (node (ref "C417") (pin "1") (pinfunction "1_1") (pintype "passive"))
      (node (ref "C418") (pin "1") (pinfunction "1_1") (pintype "passive"))
      (node (ref "C419") (pin "1") (pinfunction "1_1") (pintype "passive"))
      (node (ref "C420") (pin "1") (pinfunction "1_1") (pintype "passive"))
      (node (ref "C421") (pin "1") (pinfunction "1_1") (pintype "passive"))
      (node (ref "IC25") (pin "C2") (pinfunction "EN_C2") (pintype "passive"))
      (node (ref "IC25") (pin "D1") (pinfunction "GND_D1") (pintype "passive"))
      (node (ref "IC25") (pin "D2") (pinfunction "GND_D2") (pintype "passive"))
      (node (ref "IC25") (pin "D3") (pinfunction "DF_IN_D3") (pintype "passive"))
      (node (ref "IC26") (pin "4") (pinfunction "GND_4") (pintype "passive"))
      (node (ref "IC26") (pin "9") (pinfunction "PAD_9") (pintype "passive"))
      (node (ref "IC27") (pin "10") (pinfunction "PGND_10") (pintype "passive"))
      (node (ref "IC27") (pin "11") (pinfunction "PGND_11") (pintype "passive"))
      (node (ref "IC27") (pin "12") (pinfunction "PGND_12") (pintype "passive"))
      (node (ref "IC27") (pin "13") (pinfunction "PGND_13") (pintype "passive"))
      (node (ref "IC27") (pin "25") (pinfunction "GND_25") (pintype "passive"))
      (node (ref "IC27") (pin "4") (pinfunction "GND_4") (pintype "passive"))
      (node (ref "IC27") (pin "8") (pinfunction "PGND_8") (pintype "passive"))
      (node (ref "IC27") (pin "9") (pinfunction "PGND_9") (pintype "passive"))
      (node (ref "IC28") (pin "4") (pinfunction "GND_4") (pintype "passive"))
      (node (ref "IC28") (pin "9") (pinfunction "PAD_9") (pintype "passive"))
      (node (ref "IC29") (pin "11") (pinfunction "GND_11") (pintype "passive"))
      (node (ref "IC29") (pin "4") (pinfunction "PGND_4") (pintype "passive"))
      (node (ref "IC29") (pin "8") (pinfunction "GND_8") (pintype "passive"))
      (node (ref "IC30") (pin "4") (pinfunction "GND_4") (pintype "passive"))
      (node (ref "IC30") (pin "9") (pinfunction "PAD_9") (pintype "passive"))
      (node (ref "IC31") (pin "10") (pinfunction "PGND_10") (pintype "passive"))
      (node (ref "IC31") (pin "11") (pinfunction "PGND_11") (pintype "passive"))
      (node (ref "IC31") (pin "12") (pinfunction "PGND_12") (pintype "passive"))
      (node (ref "IC31") (pin "13") (pinfunction "PGND_13") (pintype "passive"))
      (node (ref "IC31") (pin "25") (pinfunction "GND_25") (pintype "passive"))
      (node (ref "IC31") (pin "4") (pinfunction "GND_4") (pintype "passive"))
      (node (ref "IC31") (pin "8") (pinfunction "PGND_8") (pintype "passive"))
      (node (ref "IC31") (pin "9") (pinfunction "PGND_9") (pintype "passive"))
      (node (ref "IC32") (pin "4") (pinfunction "GND_4") (pintype "passive"))
      (node (ref "IC32") (pin "9") (pinfunction "PAD_9") (pintype "passive"))
      (node (ref "IC33") (pin "4") (pinfunction "GND_4") (pintype "passive"))
      (node (ref "IC33") (pin "9") (pinfunction "PAD_9") (pintype "passive"))
      (node (ref "IC34") (pin "4") (pinfunction "GND_4") (pintype "passive"))
      (node (ref "IC34") (pin "9") (pinfunction "PAD_9") (pintype "passive"))
      (node (ref "IC35") (pin "3") (pinfunction "GND_3") (pintype "passive"))
      (node (ref "IC36") (pin "7") (pinfunction "GND_7") (pintype "passive"))
      (node (ref "IC36") (pin "9") (pinfunction "PAD_9") (pintype "passive"))
      (node (ref "J20") (pin "2") (pinfunction "2_2") (pintype "passive"))
      (node (ref "J20") (pin "3") (pinfunction "3_3") (pintype "passive"))
      (node (ref "J21") (pin "1") (pinfunction "1_1") (pintype "passive"))
      (node (ref "LED8") (pin "3") (pinfunction "3_3") (pintype "power_in"))
      (node (ref "LEDS2") (pin "K2") (pinfunction "C_K2") (pintype "power_in"))
      (node (ref "MECH1") (pin "MH1") (pinfunction "MH1_MH1") (pintype "passive"))
      (node (ref "MECH2") (pin "MH1") (pinfunction "MH1_MH1") (pintype "passive"))
      (node (ref "MECH3") (pin "MH1") (pinfunction "MH1_MH1") (pintype "passive"))
      (node (ref "MECH4") (pin "MH1") (pinfunction "MH1_MH1") (pintype "passive"))
      (node (ref "R175") (pin "2") (pinfunction "2_2") (pintype "passive"))
      (node (ref "R181") (pin "2") (pinfunction "2_2") (pintype "passive"))
      (node (ref "R182") (pin "2") (pinfunction "2_2") (pintype "passive"))
      (node (ref "R183") (pin "2") (pinfunction "2_2") (pintype "passive"))
      (node (ref "R184") (pin "1") (pinfunction "1_1") (pintype "passive"))
      (node (ref "R190") (pin "1") (pinfunction "1_1") (pintype "passive"))
      (node (ref "R196") (pin "2") (pinfunction "2_2") (pintype "passive"))
      (node (ref "R197") (pin "2") (pinfunction "2_2") (pintype "passive"))
      (node (ref "R198") (pin "1") (pinfunction "1_1") (pintype "passive"))
      (node (ref "R199") (pin "2") (pinfunction "2_2") (pintype "passive"))
      (node (ref "R200") (pin "2") (pinfunction "2_2") (pintype "passive"))
      (node (ref "R206") (pin "2") (pinfunction "2_2") (pintype "passive"))
      (node (ref "R207") (pin "2") (pinfunction "2_2") (pintype "passive"))
      (node (ref "R210") (pin "1") (pinfunction "1_1") (pintype "passive"))
    )
    (net (code "9") (name "Net-(C367-Pad2)") (class "Default")
      (node (ref "C367") (pin "2") (pinfunction "2_2") (pintype "passive"))
      (node (ref "FR56") (pin "2") (pinfunction "2_2") (pintype "passive"))
      (node (ref "IC25") (pin "A2") (pinfunction "Vout_A2") (pintype "passive"))
      (node (ref "IC25") (pin "A3") (pinfunction "Vout_A3") (pintype "passive"))
      (node (ref "IC25") (pin "B3") (pinfunction "Vout_B3") (pintype "passive"))
      (node (ref "IC25") (pin "C3") (pinfunction "Vout_C3") (pintype "passive"))
    )
    (net (code "10") (name "Net-(C373-Pad1)") (class "Default")
      (node (ref "C373") (pin "1") (pinfunction "1_1") (pintype "passive"))
      (node (ref "J20") (pin "1") (pinfunction "1_1") (pintype "passive"))
      (node (ref "J21") (pin "2") (pinfunction "2_2") (pintype "passive"))
      (node (ref "R172") (pin "2") (pinfunction "2_2") (pintype "passive"))
      (node (ref "VD1") (pin "A") (pinfunction "A_A") (pintype "passive"))
    )
    (net (code "11") (name "Net-(C378-Pad2)") (class "Default")
      (node (ref "C378") (pin "2") (pinfunction "2_2") (pintype "passive"))
      (node (ref "IC27") (pin "14") (pinfunction "SW_14") (pintype "passive"))
      (node (ref "IC27") (pin "26") (pinfunction "SW_26") (pintype "passive"))
      (node (ref "IC27") (pin "5") (pinfunction "SW_5") (pintype "passive"))
      (node (ref "IC27") (pin "6") (pinfunction "SW_6") (pintype "passive"))
      (node (ref "IC27") (pin "7") (pinfunction "SW_7") (pintype "passive"))
      (node (ref "L1") (pin "1") (pinfunction "1_1") (pintype "passive"))
    )
    (net (code "12") (name "Net-(C390-Pad1)") (class "Default")
      (node (ref "C390") (pin "1") (pinfunction "1_1") (pintype "passive"))
      (node (ref "R185") (pin "1") (pinfunction "1_1") (pintype "passive"))
    )
    (net (code "13") (name "Net-(C399-Pad2)") (class "Default")
      (node (ref "C399") (pin "2") (pinfunction "2_2") (pintype "passive"))
      (node (ref "IC31") (pin "14") (pinfunction "SW_14") (pintype "passive"))
      (node (ref "IC31") (pin "26") (pinfunction "SW_26") (pintype "passive"))
      (node (ref "IC31") (pin "5") (pinfunction "SW_5") (pintype "passive"))
      (node (ref "IC31") (pin "6") (pinfunction "SW_6") (pintype "passive"))
      (node (ref "IC31") (pin "7") (pinfunction "SW_7") (pintype "passive"))
      (node (ref "L2") (pin "1") (pinfunction "1_1") (pintype "passive"))
    )
    (net (code "14") (name "Net-(C412-Pad1)") (class "Default")
      (node (ref "C412") (pin "1") (pinfunction "1_1") (pintype "passive"))
      (node (ref "R201") (pin "1") (pinfunction "1_1") (pintype "passive"))
    )
    (net (code "15") (name "Net-(C418-Pad2)") (class "Default")
      (node (ref "C418") (pin "2") (pinfunction "2_2") (pintype "passive"))
      (node (ref "FR63") (pin "2") (pinfunction "2_2") (pintype "passive"))
      (node (ref "R208") (pin "2") (pinfunction "2_2") (pintype "passive"))
    )
    (net (code "16") (name "Net-(IC26-ADJ{slash}NC)") (class "Default")
      (node (ref "IC26") (pin "3") (pinfunction "ADJ/NC_3") (pintype "passive"))
      (node (ref "R174") (pin "1") (pinfunction "1_1") (pintype "passive"))
      (node (ref "R175") (pin "1") (pinfunction "1_1") (pintype "passive"))
    )
    (net (code "17") (name "Net-(IC26-OUT)") (class "Default")
      (node (ref "C377") (pin "2") (pinfunction "2_2") (pintype "passive"))
      (node (ref "IC26") (pin "1") (pinfunction "OUT_1") (pintype "output"))
      (node (ref "R173") (pin "2") (pinfunction "2_2") (pintype "passive"))
      (node (ref "R174") (pin "2") (pinfunction "2_2") (pintype "passive"))
    )
    (net (code "18") (name "Net-(IC27-BST)") (class "Default")
      (node (ref "C378") (pin "1") (pinfunction "1_1") (pintype "passive"))
      (node (ref "IC27") (pin "15") (pinfunction "BST_15") (pintype "passive"))
    )
    (net (code "19") (name "Net-(IC27-COMP)") (class "Default")
      (node (ref "C389") (pin "1") (pinfunction "1_1") (pintype "passive"))
      (node (ref "IC27") (pin "1") (pinfunction "COMP_1") (pintype "passive"))
      (node (ref "R185") (pin "2") (pinfunction "2_2") (pintype "passive"))
    )
    (net (code "20") (name "Net-(IC27-FB)") (class "Default")
      (node (ref "IC27") (pin "2") (pinfunction "FB_2") (pintype "passive"))
      (node (ref "R180") (pin "2") (pinfunction "2_2") (pintype "passive"))
      (node (ref "R184") (pin "2") (pinfunction "2_2") (pintype "passive"))
    )
    (net (code "21") (name "Net-(IC27-RT)") (class "Default")
      (node (ref "IC27") (pin "22") (pinfunction "RT_22") (pintype "passive"))
      (node (ref "R183") (pin "1") (pinfunction "1_1") (pintype "passive"))
    )
    (net (code "22") (name "Net-(IC27-SS)") (class "Default")
      (node (ref "C391") (pin "1") (pinfunction "1_1") (pintype "passive"))
      (node (ref "IC27") (pin "24") (pinfunction "SS_24") (pintype "passive"))
    )
    (net (code "23") (name "Net-(IC27-SYNC)") (class "Default")
      (node (ref "IC27") (pin "23") (pinfunction "SYNC_23") (pintype "passive"))
      (node (ref "R181") (pin "1") (pinfunction "1_1") (pintype "passive"))
    )
    (net (code "24") (name "Net-(IC27-VREG)") (class "Default")
      (node (ref "C388") (pin "1") (pinfunction "1_1") (pintype "passive"))
      (node (ref "IC27") (pin "3") (pinfunction "VREG_3") (pintype "passive"))
    )
    (net (code "25") (name "Net-(IC28-ADJ{slash}NC)") (class "Default")
      (node (ref "IC28") (pin "3") (pinfunction "ADJ/NC_3") (pintype "passive"))
      (node (ref "R179") (pin "1") (pinfunction "1_1") (pintype "passive"))
      (node (ref "R182") (pin "1") (pinfunction "1_1") (pintype "passive"))
    )
    (net (code "26") (name "Net-(IC28-EN)") (class "Default")
      (node (ref "C383") (pin "2") (pinfunction "2_2") (pintype "passive"))
      (node (ref "FR58") (pin "2") (pinfunction "2_2") (pintype "passive"))
      (node (ref "IC28") (pin "5") (pinfunction "EN_5") (pintype "input"))
      (node (ref "IC28") (pin "8") (pinfunction "IN_8") (pintype "input"))
    )
    (net (code "27") (name "Net-(IC28-OUT)") (class "Default")
      (node (ref "C384") (pin "2") (pinfunction "2_2") (pintype "passive"))
      (node (ref "IC28") (pin "1") (pinfunction "OUT_1") (pintype "output"))
      (node (ref "R178") (pin "2") (pinfunction "2_2") (pintype "passive"))
      (node (ref "R179") (pin "2") (pinfunction "2_2") (pintype "passive"))
    )
    (net (code "28") (name "Net-(IC29-S3)") (class "Default")
      (node (ref "IC29") (pin "7") (pinfunction "S3_7") (pintype "passive"))
      (node (ref "R187") (pin "2") (pinfunction "2_2") (pintype "passive"))
    )
    (net (code "29") (name "Net-(IC29-S5)") (class "Default")
      (node (ref "IC29") (pin "9") (pinfunction "S5_9") (pintype "passive"))
      (node (ref "R186") (pin "2") (pinfunction "2_2") (pintype "passive"))
    )
    (net (code "30") (name "Net-(IC30-ADJ{slash}NC)") (class "Default")
      (node (ref "IC30") (pin "3") (pinfunction "ADJ/NC_3") (pintype "passive"))
      (node (ref "R189") (pin "2") (pinfunction "2_2") (pintype "passive"))
      (node (ref "R190") (pin "2") (pinfunction "2_2") (pintype "passive"))
    )
    (net (code "31") (name "Net-(IC30-EN)") (class "Default")
      (node (ref "C397") (pin "2") (pinfunction "2_2") (pintype "passive"))
      (node (ref "FR59") (pin "2") (pinfunction "2_2") (pintype "passive"))
      (node (ref "IC30") (pin "5") (pinfunction "EN_5") (pintype "input"))
      (node (ref "IC30") (pin "8") (pinfunction "IN_8") (pintype "input"))
    )
    (net (code "32") (name "Net-(IC30-OUT)") (class "Default")
      (node (ref "C398") (pin "2") (pinfunction "2_2") (pintype "passive"))
      (node (ref "IC30") (pin "1") (pinfunction "OUT_1") (pintype "output"))
      (node (ref "R188") (pin "2") (pinfunction "2_2") (pintype "passive"))
      (node (ref "R189") (pin "1") (pinfunction "1_1") (pintype "passive"))
    )
    (net (code "33") (name "Net-(IC31-BST)") (class "Default")
      (node (ref "C399") (pin "1") (pinfunction "1_1") (pintype "passive"))
      (node (ref "IC31") (pin "15") (pinfunction "BST_15") (pintype "passive"))
    )
    (net (code "34") (name "Net-(IC31-COMP)") (class "Default")
      (node (ref "C411") (pin "1") (pinfunction "1_1") (pintype "passive"))
      (node (ref "IC31") (pin "1") (pinfunction "COMP_1") (pintype "passive"))
      (node (ref "R201") (pin "2") (pinfunction "2_2") (pintype "passive"))
    )
    (net (code "35") (name "Net-(IC31-FB)") (class "Default")
      (node (ref "IC31") (pin "2") (pinfunction "FB_2") (pintype "passive"))
      (node (ref "R195") (pin "2") (pinfunction "2_2") (pintype "passive"))
      (node (ref "R200") (pin "1") (pinfunction "1_1") (pintype "passive"))
    )
    (net (code "36") (name "Net-(IC31-RT)") (class "Default")
      (node (ref "IC31") (pin "22") (pinfunction "RT_22") (pintype "passive"))
      (node (ref "R199") (pin "1") (pinfunction "1_1") (pintype "passive"))
    )
    (net (code "37") (name "Net-(IC31-SS)") (class "Default")
      (node (ref "C413") (pin "1") (pinfunction "1_1") (pintype "passive"))
      (node (ref "IC31") (pin "24") (pinfunction "SS_24") (pintype "passive"))
    )
    (net (code "38") (name "Net-(IC31-SYNC)") (class "Default")
      (node (ref "IC31") (pin "23") (pinfunction "SYNC_23") (pintype "passive"))
      (node (ref "R196") (pin "1") (pinfunction "1_1") (pintype "passive"))
    )
    (net (code "39") (name "Net-(IC31-VREG)") (class "Default")
      (node (ref "C408") (pin "1") (pinfunction "1_1") (pintype "passive"))
      (node (ref "IC31") (pin "3") (pinfunction "VREG_3") (pintype "passive"))
    )
    (net (code "40") (name "Net-(IC32-ADJ{slash}NC)") (class "Default")
      (node (ref "IC32") (pin "3") (pinfunction "ADJ/NC_3") (pintype "passive"))
      (node (ref "R193") (pin "1") (pinfunction "1_1") (pintype "passive"))
      (node (ref "R197") (pin "1") (pinfunction "1_1") (pintype "passive"))
    )
    (net (code "41") (name "Net-(IC32-OUT)") (class "Default")
      (node (ref "C402") (pin "2") (pinfunction "2_2") (pintype "passive"))
      (node (ref "IC32") (pin "1") (pinfunction "OUT_1") (pintype "output"))
      (node (ref "R191") (pin "2") (pinfunction "2_2") (pintype "passive"))
      (node (ref "R193") (pin "2") (pinfunction "2_2") (pintype "passive"))
    )
    (net (code "42") (name "Net-(IC33-ADJ{slash}NC)") (class "Default")
      (node (ref "IC33") (pin "3") (pinfunction "ADJ/NC_3") (pintype "passive"))
      (node (ref "R194") (pin "1") (pinfunction "1_1") (pintype "passive"))
      (node (ref "R198") (pin "2") (pinfunction "2_2") (pintype "passive"))
    )
    (net (code "43") (name "Net-(IC33-EN)") (class "Default")
      (node (ref "C404") (pin "2") (pinfunction "2_2") (pintype "passive"))
      (node (ref "FR60") (pin "2") (pinfunction "2_2") (pintype "passive"))
      (node (ref "IC33") (pin "5") (pinfunction "EN_5") (pintype "input"))
      (node (ref "IC33") (pin "8") (pinfunction "IN_8") (pintype "input"))
    )
    (net (code "44") (name "Net-(IC33-OUT)") (class "Default")
      (node (ref "C405") (pin "2") (pinfunction "2_2") (pintype "passive"))
      (node (ref "IC33") (pin "1") (pinfunction "OUT_1") (pintype "output"))
      (node (ref "R192") (pin "2") (pinfunction "2_2") (pintype "passive"))
      (node (ref "R194") (pin "2") (pinfunction "2_2") (pintype "passive"))
    )
    (net (code "45") (name "Net-(IC34-ADJ{slash}NC)") (class "Default")
      (node (ref "IC34") (pin "3") (pinfunction "ADJ/NC_3") (pintype "passive"))
      (node (ref "R203") (pin "1") (pinfunction "1_1") (pintype "passive"))
      (node (ref "R206") (pin "1") (pinfunction "1_1") (pintype "passive"))
    )
    (net (code "46") (name "Net-(IC34-OUT)") (class "Default")
      (node (ref "C410") (pin "2") (pinfunction "2_2") (pintype "passive"))
      (node (ref "IC34") (pin "1") (pinfunction "OUT_1") (pintype "output"))
      (node (ref "R202") (pin "2") (pinfunction "2_2") (pintype "passive"))
      (node (ref "R203") (pin "2") (pinfunction "2_2") (pintype "passive"))
    )
    (net (code "47") (name "Net-(IC35-ADJUST)") (class "Default")
      (node (ref "IC35") (pin "5") (pinfunction "ADJUST_5") (pintype "passive"))
      (node (ref "R205") (pin "2") (pinfunction "2_2") (pintype "passive"))
      (node (ref "R207") (pin "1") (pinfunction "1_1") (pintype "passive"))
    )
    (net (code "48") (name "Net-(IC35-IN)") (class "Default")
      (node (ref "C416") (pin "2") (pinfunction "2_2") (pintype "passive"))
      (node (ref "FR61") (pin "2") (pinfunction "2_2") (pintype "passive"))
      (node (ref "IC35") (pin "2") (pinfunction "IN_2") (pintype "passive"))
    )
    (net (code "49") (name "Net-(IC35-OUT)") (class "Default")
      (node (ref "C415") (pin "2") (pinfunction "2_2") (pintype "passive"))
      (node (ref "IC35") (pin "4") (pinfunction "OUT_4") (pintype "passive"))
      (node (ref "R204") (pin "2") (pinfunction "2_2") (pintype "passive"))
      (node (ref "R205") (pin "1") (pinfunction "1_1") (pintype "passive"))
    )
    (net (code "50") (name "Net-(IC36-ADJ{slash}BYP)") (class "Default")
      (node (ref "IC36") (pin "8") (pinfunction "ADJ/BYP_8") (pintype "input"))
      (node (ref "R209") (pin "2") (pinfunction "2_2") (pintype "passive"))
      (node (ref "R210") (pin "2") (pinfunction "2_2") (pintype "passive"))
    )
    (net (code "51") (name "Net-(IC36-EN)") (class "Default")
      (node (ref "C421") (pin "2") (pinfunction "2_2") (pintype "passive"))
      (node (ref "IC36") (pin "1") (pinfunction "EN_1") (pintype "input"))
      (node (ref "R211") (pin "2") (pinfunction "2_2") (pintype "passive"))
      (node (ref "R212") (pin "1") (pinfunction "1_1") (pintype "passive"))
    )
    (net (code "52") (name "Net-(IC36-VIN)") (class "Default")
      (node (ref "C420") (pin "2") (pinfunction "2_2") (pintype "passive"))
      (node (ref "FR62") (pin "2") (pinfunction "2_2") (pintype "passive"))
      (node (ref "IC36") (pin "3") (pinfunction "VIN_3") (pintype "input"))
    )
    (net (code "53") (name "Net-(IC36-VOUT)") (class "Default")
      (node (ref "C417") (pin "2") (pinfunction "2_2") (pintype "passive"))
      (node (ref "FR63") (pin "1") (pinfunction "1_1") (pintype "passive"))
      (node (ref "IC36") (pin "5") (pinfunction "VOUT_5") (pintype "output"))
      (node (ref "R209") (pin "1") (pinfunction "1_1") (pintype "passive"))
    )
    (net (code "54") (name "Net-(LED1-Pad1)") (class "Default")
      (node (ref "LED1") (pin "1") (pinfunction "1_1") (pintype "power_in"))
      (node (ref "LED1") (pin "4") (pinfunction "4_4") (pintype "power_in"))
      (node (ref "LEDS1") (pin "A1") (pinfunction "A_A1") (pintype "power_in"))
      (node (ref "R168") (pin "2") (pinfunction "2_2") (pintype "passive"))
    )
    (net (code "55") (name "Net-(LED2-Pad1)") (class "Default")
      (node (ref "LED2") (pin "1") (pinfunction "1_1") (pintype "power_in"))
      (node (ref "LED2") (pin "4") (pinfunction "4_4") (pintype "power_in"))
      (node (ref "LEDS2") (pin "A1") (pinfunction "A_A1") (pintype "power_in"))
      (node (ref "R169") (pin "2") (pinfunction "2_2") (pintype "passive"))
    )
    (net (code "56") (name "Net-(LED7-Pad1)") (class "Default")
      (node (ref "LED7") (pin "1") (pinfunction "1_1") (pintype "power_in"))
      (node (ref "LED7") (pin "4") (pinfunction "4_4") (pintype "power_in"))
      (node (ref "LEDS1") (pin "A2") (pinfunction "A_A2") (pintype "power_in"))
      (node (ref "R170") (pin "2") (pinfunction "2_2") (pintype "passive"))
    )
    (net (code "57") (name "Net-(LED8-Pad1)") (class "Default")
      (node (ref "LED8") (pin "1") (pinfunction "1_1") (pintype "power_in"))
      (node (ref "LEDS2") (pin "A2") (pinfunction "A_A2") (pintype "power_in"))
      (node (ref "R171") (pin "2") (pinfunction "2_2") (pintype "passive"))
    )
    (net (code "58") (name "VCC1P2") (class "Default")
      (node (ref "C406") (pin "2") (pinfunction "2_2") (pintype "passive"))
      (node (ref "C407") (pin "2") (pinfunction "2_2") (pintype "passive"))
      (node (ref "L2") (pin "2") (pinfunction "2_2") (pintype "passive"))
      (node (ref "R195") (pin "1") (pinfunction "1_1") (pintype "passive"))
    )
    (net (code "59") (name "VCC1P4_LMS") (class "Default")
      (node (ref "R188") (pin "1") (pinfunction "1_1") (pintype "passive"))
    )
    (net (code "60") (name "VCC1P8") (class "Default")
      (node (ref "R202") (pin "1") (pinfunction "1_1") (pintype "passive"))
    )
    (net (code "61") (name "VCC1P8_DDR2") (class "Default")
      (node (ref "C387") (pin "2") (pinfunction "2_2") (pintype "passive"))
      (node (ref "IC29") (pin "1") (pinfunction "VDDQSNS_1") (pintype "passive"))
      (node (ref "IC29") (pin "2") (pinfunction "VLDOIN_2") (pintype "passive"))
      (node (ref "R191") (pin "1") (pinfunction "1_1") (pintype "passive"))
    )
    (net (code "62") (name "VCC1P8_LMS") (class "Default")
      (node (ref "R178") (pin "1") (pinfunction "1_1") (pintype "passive"))
    )
    (net (code "63") (name "VCC1P25_LMS") (class "Default")
      (node (ref "R192") (pin "1") (pinfunction "1_1") (pintype "passive"))
    )
    (net (code "64") (name "VCC1P25_LMS_DIG") (class "Default")
      (node (ref "R204") (pin "1") (pinfunction "1_1") (pintype "passive"))
    )
    (net (code "65") (name "VCC2P5") (class "Default")
      (node (ref "R173") (pin "1") (pinfunction "1_1") (pintype "passive"))
      (node (ref "R177") (pin "2") (pinfunction "2_2") (pintype "passive"))
      (node (ref "R211") (pin "1") (pinfunction "1_1") (pintype "passive"))
    )
    (net (code "66") (name "VCC3P3") (class "Default")
      (node (ref "C376") (pin "2") (pinfunction "2_2") (pintype "passive"))
      (node (ref "C382") (pin "2") (pinfunction "2_2") (pintype "passive"))
      (node (ref "C385") (pin "2") (pinfunction "2_2") (pintype "passive"))
      (node (ref "C386") (pin "2") (pinfunction "2_2") (pintype "passive"))
      (node (ref "C394") (pin "2") (pinfunction "2_2") (pintype "passive"))
      (node (ref "C396") (pin "2") (pinfunction "2_2") (pintype "passive"))
      (node (ref "C401") (pin "2") (pinfunction "2_2") (pintype "passive"))
      (node (ref "C403") (pin "2") (pinfunction "2_2") (pintype "passive"))
      (node (ref "C409") (pin "2") (pinfunction "2_2") (pintype "passive"))
      (node (ref "C414") (pin "2") (pinfunction "2_2") (pintype "passive"))
      (node (ref "FR58") (pin "1") (pinfunction "1_1") (pintype "passive"))
      (node (ref "FR59") (pin "1") (pinfunction "1_1") (pintype "passive"))
      (node (ref "FR60") (pin "1") (pinfunction "1_1") (pintype "passive"))
      (node (ref "FR61") (pin "1") (pinfunction "1_1") (pintype "passive"))
      (node (ref "IC26") (pin "5") (pinfunction "EN_5") (pintype "input"))
      (node (ref "IC26") (pin "8") (pinfunction "IN_8") (pintype "input"))
      (node (ref "IC29") (pin "10") (pinfunction "VIN_10") (pintype "passive"))
      (node (ref "IC32") (pin "5") (pinfunction "EN_5") (pintype "input"))
      (node (ref "IC32") (pin "8") (pinfunction "IN_8") (pintype "input"))
      (node (ref "IC34") (pin "5") (pinfunction "EN_5") (pintype "input"))
      (node (ref "IC34") (pin "8") (pinfunction "IN_8") (pintype "input"))
      (node (ref "L1") (pin "2") (pinfunction "2_2") (pintype "passive"))
      (node (ref "R171") (pin "1") (pinfunction "1_1") (pintype "passive"))
      (node (ref "R176") (pin "2") (pinfunction "2_2") (pintype "passive"))
      (node (ref "R180") (pin "1") (pinfunction "1_1") (pintype "passive"))
      (node (ref "R186") (pin "1") (pinfunction "1_1") (pintype "passive"))
      (node (ref "R187") (pin "1") (pinfunction "1_1") (pintype "passive"))
    )
    (net (code "67") (name "VCC3P3_CLK") (class "Default")
      (node (ref "R208") (pin "1") (pinfunction "1_1") (pintype "passive"))
    )
    (net (code "68") (name "VCC5P0_USB") (class "Default")
      (node (ref "C375") (pin "2") (pinfunction "2_2") (pintype "passive"))
      (node (ref "IC25") (pin "A1") (pinfunction "Vbus_A1") (pintype "passive"))
      (node (ref "IC25") (pin "B1") (pinfunction "Vbus_B1") (pintype "passive"))
      (node (ref "IC25") (pin "C1") (pinfunction "Vbus_C1") (pintype "passive"))
      (node (ref "R167") (pin "2") (pinfunction "2_2") (pintype "passive"))
    )
    (net (code "69") (name "VCC_EXT") (class "Default")
      (node (ref "C374") (pin "2") (pinfunction "2_2") (pintype "passive"))
      (node (ref "IC25") (pin "A4") (pinfunction "Vin_A4") (pintype "passive"))
      (node (ref "IC25") (pin "B4") (pinfunction "Vin_B4") (pintype "passive"))
      (node (ref "IC25") (pin "C4") (pinfunction "Vin_C4") (pintype "passive"))
      (node (ref "R166") (pin "2") (pinfunction "2_2") (pintype "passive"))
      (node (ref "R172") (pin "1") (pinfunction "1_1") (pintype "passive"))
      (node (ref "VD1") (pin "K") (pinfunction "K_K") (pintype "passive"))
    )
    (net (code "70") (name "VCC_INT") (class "Default")
      (node (ref "C368") (pin "2") (pinfunction "2_2") (pintype "passive"))
      (node (ref "C369") (pin "2") (pinfunction "2_2") (pintype "passive"))
      (node (ref "C370") (pin "2") (pinfunction "2_2") (pintype "passive"))
      (node (ref "C371") (pin "2") (pinfunction "2_2") (pintype "passive"))
      (node (ref "C372") (pin "1") (pinfunction "1_1") (pintype "passive"))
      (node (ref "C379") (pin "2") (pinfunction "2_2") (pintype "passive"))
      (node (ref "C400") (pin "2") (pinfunction "2_2") (pintype "passive"))
      (node (ref "C419") (pin "2") (pinfunction "2_2") (pintype "passive"))
      (node (ref "FR56") (pin "1") (pinfunction "1_1") (pintype "passive"))
      (node (ref "FR62") (pin "1") (pinfunction "1_1") (pintype "passive"))
      (node (ref "IC27") (pin "16") (pinfunction "PVIN_16") (pintype "passive"))
      (node (ref "IC27") (pin "17") (pinfunction "PVIN_17") (pintype "passive"))
      (node (ref "IC27") (pin "18") (pinfunction "PVIN_18") (pintype "passive"))
      (node (ref "IC27") (pin "19") (pinfunction "PVIN_19") (pintype "passive"))
      (node (ref "IC27") (pin "20") (pinfunction "EN_20") (pintype "passive"))
      (node (ref "IC31") (pin "16") (pinfunction "PVIN_16") (pintype "passive"))
      (node (ref "IC31") (pin "17") (pinfunction "PVIN_17") (pintype "passive"))
      (node (ref "IC31") (pin "18") (pinfunction "PVIN_18") (pintype "passive"))
      (node (ref "IC31") (pin "19") (pinfunction "PVIN_19") (pintype "passive"))
      (node (ref "IC31") (pin "20") (pinfunction "EN_20") (pintype "passive"))
      (node (ref "J21") (pin "3") (pinfunction "3_3") (pintype "passive"))
      (node (ref "R166") (pin "1") (pinfunction "1_1") (pintype "passive"))
      (node (ref "R167") (pin "1") (pinfunction "1_1") (pintype "passive"))
    )
    (net (code "71") (name "VDIO_LMS") (class "Default")
      (node (ref "C380") (pin "2") (pinfunction "2_2") (pintype "passive"))
      (node (ref "C381") (pin "1") (pinfunction "1_1") (pintype "passive"))
      (node (ref "FR57") (pin "2") (pinfunction "2_2") (pintype "passive"))
    )
    (net (code "72") (name "VDIO_LMS_FPGA") (class "Default")
      (node (ref "FR57") (pin "1") (pinfunction "1_1") (pintype "passive"))
      (node (ref "R176") (pin "1") (pinfunction "1_1") (pintype "passive"))
      (node (ref "R177") (pin "1") (pinfunction "1_1") (pintype "passive"))
      (node (ref "R212") (pin "2") (pinfunction "2_2") (pintype "passive"))
    )
    (net (code "73") (name "VREF_DDR2") (class "Default")
      (node (ref "C395") (pin "1") (pinfunction "1_1") (pintype "passive"))
      (node (ref "IC29") (pin "6") (pinfunction "VTTREF_6") (pintype "passive"))
    )
    (net (code "74") (name "VTT_DDR2") (class "Default")
      (node (ref "C392") (pin "2") (pinfunction "2_2") (pintype "passive"))
      (node (ref "C393") (pin "2") (pinfunction "2_2") (pintype "passive"))
      (node (ref "IC29") (pin "3") (pinfunction "VTT_3") (pintype "passive"))
      (node (ref "IC29") (pin "5") (pinfunction "VTTSNS_5") (pintype "passive"))
    )
    (net (code "75") (name "unconnected-(F1-Pad1)") (class "Default")
      (node (ref "F1") (pin "1") (pintype "passive+no_connect"))
    )
    (net (code "76") (name "unconnected-(F2-Pad1)") (class "Default")
      (node (ref "F2") (pin "1") (pintype "passive+no_connect"))
    )
    (net (code "77") (name "unconnected-(F3-Pad1)") (class "Default")
      (node (ref "F3") (pin "1") (pintype "passive+no_connect"))
    )
    (net (code "78") (name "unconnected-(F4-Pad1)") (class "Default")
      (node (ref "F4") (pin "1") (pintype "passive+no_connect"))
    )
    (net (code "79") (name "unconnected-(IC25-Other_Vin_AVA-PadB2)") (class "Default")
      (node (ref "IC25") (pin "B2") (pinfunction "Other_Vin_AVA_B2") (pintype "passive+no_connect"))
    )
    (net (code "80") (name "unconnected-(IC26-NC-Pad2)") (class "Default")
      (node (ref "IC26") (pin "2") (pinfunction "NC_2") (pintype "passive+no_connect"))
    )
    (net (code "81") (name "unconnected-(IC26-NC-Pad6)") (class "Default")
      (node (ref "IC26") (pin "6") (pinfunction "NC_6") (pintype "passive+no_connect"))
    )
    (net (code "82") (name "unconnected-(IC26-NC-Pad7)") (class "Default")
      (node (ref "IC26") (pin "7") (pinfunction "NC_7") (pintype "passive+no_connect"))
    )
    (net (code "83") (name "unconnected-(IC27-PGOOD-Pad21)") (class "Default")
      (node (ref "IC27") (pin "21") (pinfunction "PGOOD_21") (pintype "passive+no_connect"))
    )
    (net (code "84") (name "unconnected-(IC28-NC-Pad2)") (class "Default")
      (node (ref "IC28") (pin "2") (pinfunction "NC_2") (pintype "passive+no_connect"))
    )
    (net (code "85") (name "unconnected-(IC28-NC-Pad6)") (class "Default")
      (node (ref "IC28") (pin "6") (pinfunction "NC_6") (pintype "passive+no_connect"))
    )
    (net (code "86") (name "unconnected-(IC28-NC-Pad7)") (class "Default")
      (node (ref "IC28") (pin "7") (pinfunction "NC_7") (pintype "passive+no_connect"))
    )
    (net (code "87") (name "unconnected-(IC30-NC-Pad2)") (class "Default")
      (node (ref "IC30") (pin "2") (pinfunction "NC_2") (pintype "passive+no_connect"))
    )
    (net (code "88") (name "unconnected-(IC30-NC-Pad6)") (class "Default")
      (node (ref "IC30") (pin "6") (pinfunction "NC_6") (pintype "passive+no_connect"))
    )
    (net (code "89") (name "unconnected-(IC30-NC-Pad7)") (class "Default")
      (node (ref "IC30") (pin "7") (pinfunction "NC_7") (pintype "passive+no_connect"))
    )
    (net (code "90") (name "unconnected-(IC31-PGOOD-Pad21)") (class "Default")
      (node (ref "IC31") (pin "21") (pinfunction "PGOOD_21") (pintype "passive+no_connect"))
    )
    (net (code "91") (name "unconnected-(IC32-NC-Pad2)") (class "Default")
      (node (ref "IC32") (pin "2") (pinfunction "NC_2") (pintype "passive+no_connect"))
    )
    (net (code "92") (name "unconnected-(IC32-NC-Pad6)") (class "Default")
      (node (ref "IC32") (pin "6") (pinfunction "NC_6") (pintype "passive+no_connect"))
    )
    (net (code "93") (name "unconnected-(IC32-NC-Pad7)") (class "Default")
      (node (ref "IC32") (pin "7") (pinfunction "NC_7") (pintype "passive+no_connect"))
    )
    (net (code "94") (name "unconnected-(IC33-NC-Pad2)") (class "Default")
      (node (ref "IC33") (pin "2") (pinfunction "NC_2") (pintype "passive+no_connect"))
    )
    (net (code "95") (name "unconnected-(IC33-NC-Pad6)") (class "Default")
      (node (ref "IC33") (pin "6") (pinfunction "NC_6") (pintype "passive+no_connect"))
    )
    (net (code "96") (name "unconnected-(IC33-NC-Pad7)") (class "Default")
      (node (ref "IC33") (pin "7") (pinfunction "NC_7") (pintype "passive+no_connect"))
    )
    (net (code "97") (name "unconnected-(IC34-NC-Pad2)") (class "Default")
      (node (ref "IC34") (pin "2") (pinfunction "NC_2") (pintype "passive+no_connect"))
    )
    (net (code "98") (name "unconnected-(IC34-NC-Pad6)") (class "Default")
      (node (ref "IC34") (pin "6") (pinfunction "NC_6") (pintype "passive+no_connect"))
    )
    (net (code "99") (name "unconnected-(IC34-NC-Pad7)") (class "Default")
      (node (ref "IC34") (pin "7") (pinfunction "NC_7") (pintype "passive+no_connect"))
    )
    (net (code "100") (name "unconnected-(IC35-NC-Pad1)") (class "Default")
      (node (ref "IC35") (pin "1") (pinfunction "NC_1") (pintype "passive+no_connect"))
    )
    (net (code "101") (name "unconnected-(IC36-NC-Pad2)") (class "Default")
      (node (ref "IC36") (pin "2") (pinfunction "NC_2") (pintype "passive+no_connect"))
    )
    (net (code "102") (name "unconnected-(IC36-NC-Pad4)") (class "Default")
      (node (ref "IC36") (pin "4") (pinfunction "NC_4") (pintype "passive+no_connect"))
    )
    (net (code "103") (name "unconnected-(IC36-NC-Pad6)") (class "Default")
      (node (ref "IC36") (pin "6") (pinfunction "NC_6") (pintype "passive+no_connect"))
    )
    (net (code "104") (name "unconnected-(LED3-C-PadK)") (class "Default")
      (node (ref "LED3") (pin "K") (pinfunction "C_K") (pintype "power_in+no_connect"))
    )
    (net (code "105") (name "unconnected-(LED3-PadA)") (class "Default")
      (node (ref "LED3") (pin "A") (pinfunction "A_A") (pintype "power_in+no_connect"))
    )
    (net (code "106") (name "unconnected-(LED4-C-PadK)") (class "Default")
      (node (ref "LED4") (pin "K") (pinfunction "C_K") (pintype "power_in+no_connect"))
    )
    (net (code "107") (name "unconnected-(LED4-PadA)") (class "Default")
      (node (ref "LED4") (pin "A") (pinfunction "A_A") (pintype "power_in+no_connect"))
    )
    (net (code "108") (name "unconnected-(LED5-C-PadK)") (class "Default")
      (node (ref "LED5") (pin "K") (pinfunction "C_K") (pintype "power_in+no_connect"))
    )
    (net (code "109") (name "unconnected-(LED5-PadA)") (class "Default")
      (node (ref "LED5") (pin "A") (pinfunction "A_A") (pintype "power_in+no_connect"))
    )
    (net (code "110") (name "unconnected-(LED6-C-PadK)") (class "Default")
      (node (ref "LED6") (pin "K") (pinfunction "C_K") (pintype "power_in+no_connect"))
    )
    (net (code "111") (name "unconnected-(LED6-PadA)") (class "Default")
      (node (ref "LED6") (pin "A") (pinfunction "A_A") (pintype "power_in+no_connect"))
    )
    (net (code "112") (name "unconnected-(LED8-Pad2)") (class "Default")
      (node (ref "LED8") (pin "2") (pinfunction "2_2") (pintype "power_in+no_connect"))
    )
    (net (code "113") (name "unconnected-(LED8-Pad4)") (class "Default")
      (node (ref "LED8") (pin "4") (pinfunction "4_4") (pintype "power_in+no_connect"))
    )
  )
)
